# kulgurpowerMCU3-unrouted.net
KiCad netlist of a schematic drawn in EAGLE
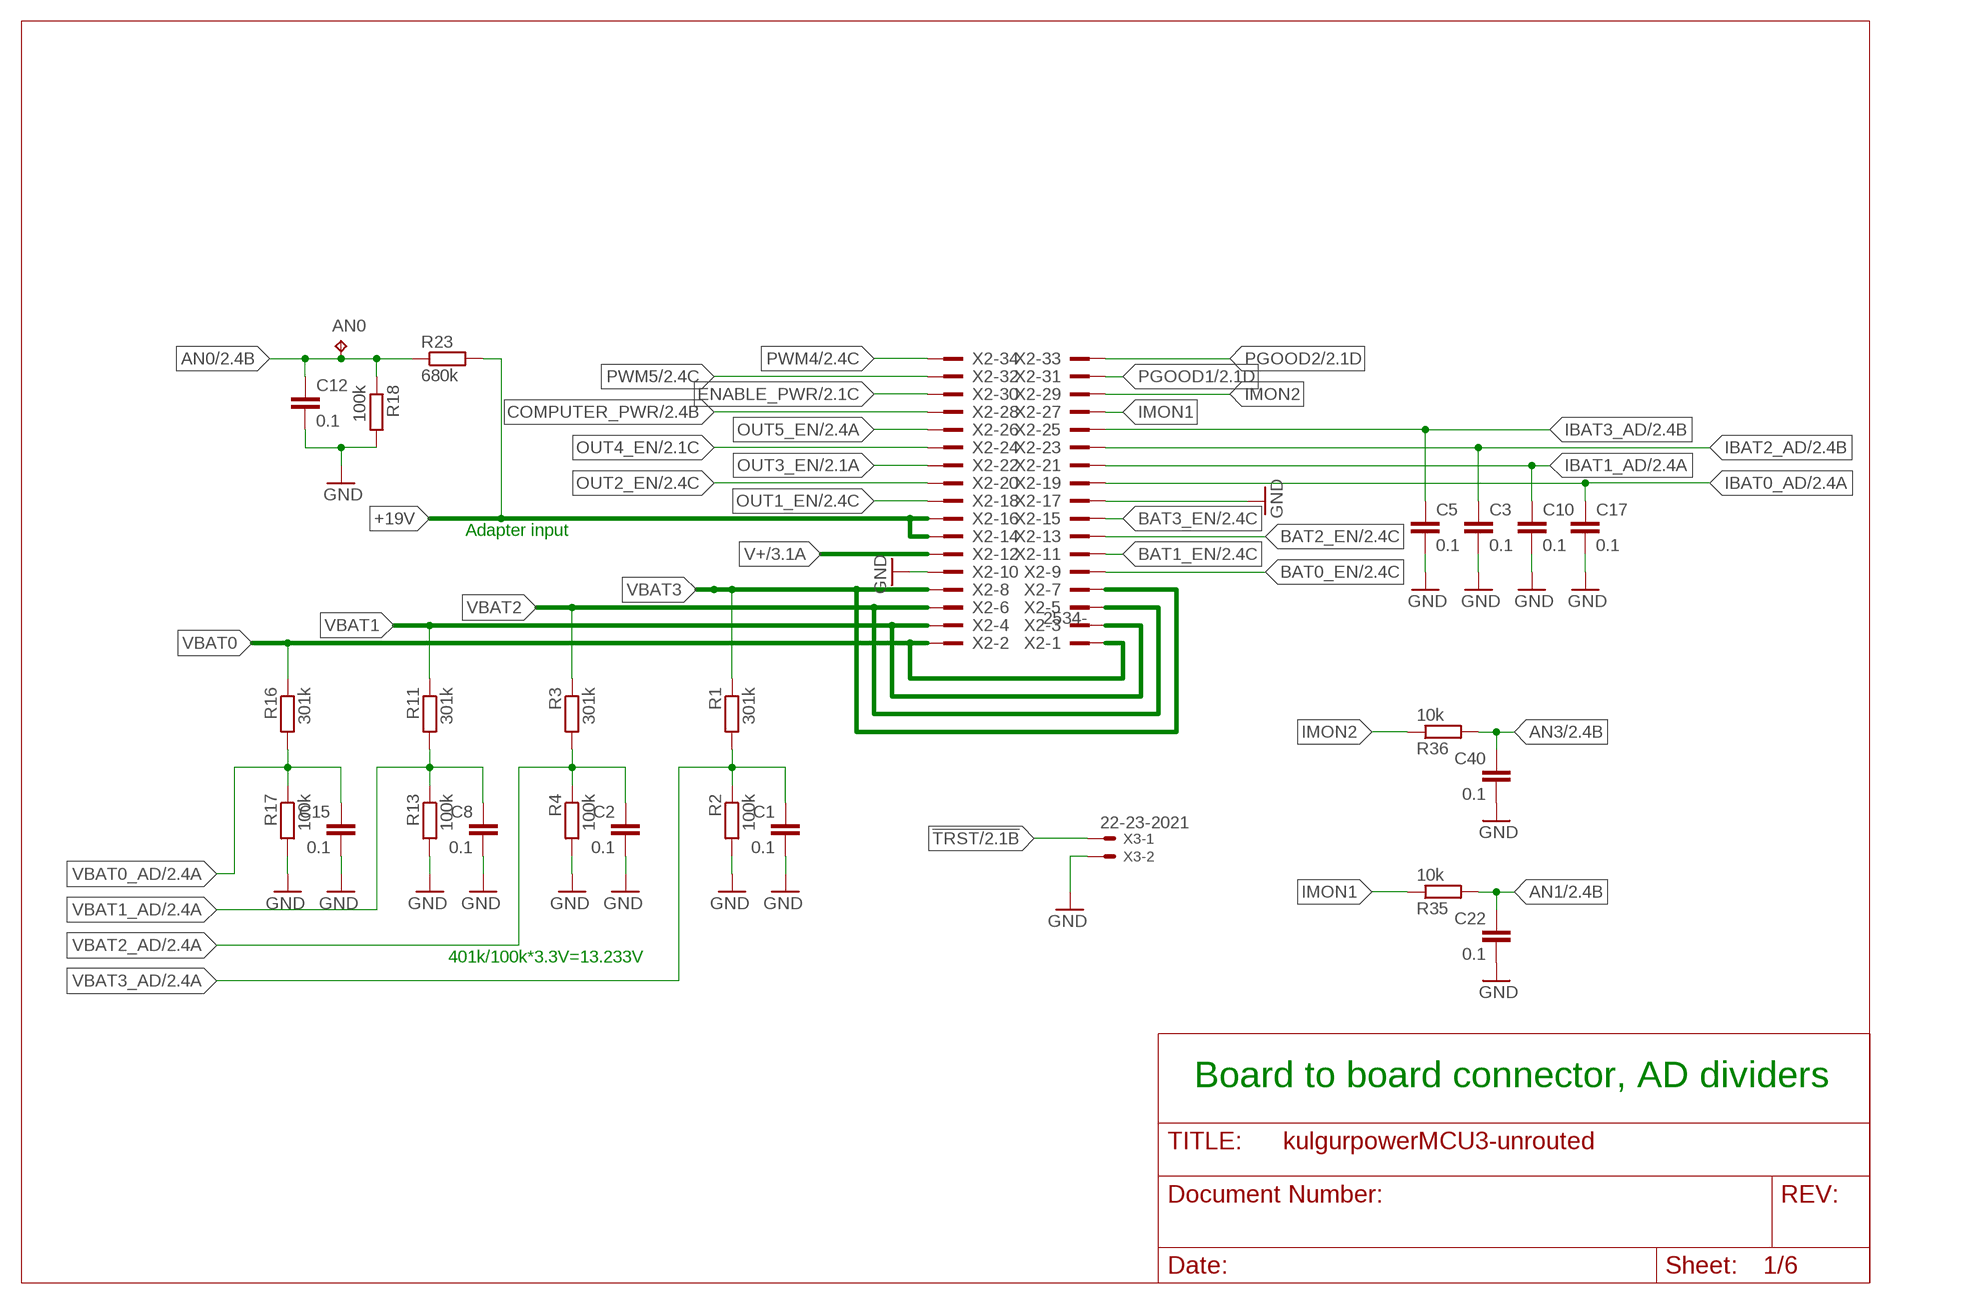
[diagram p0: schematic, sheet 1]
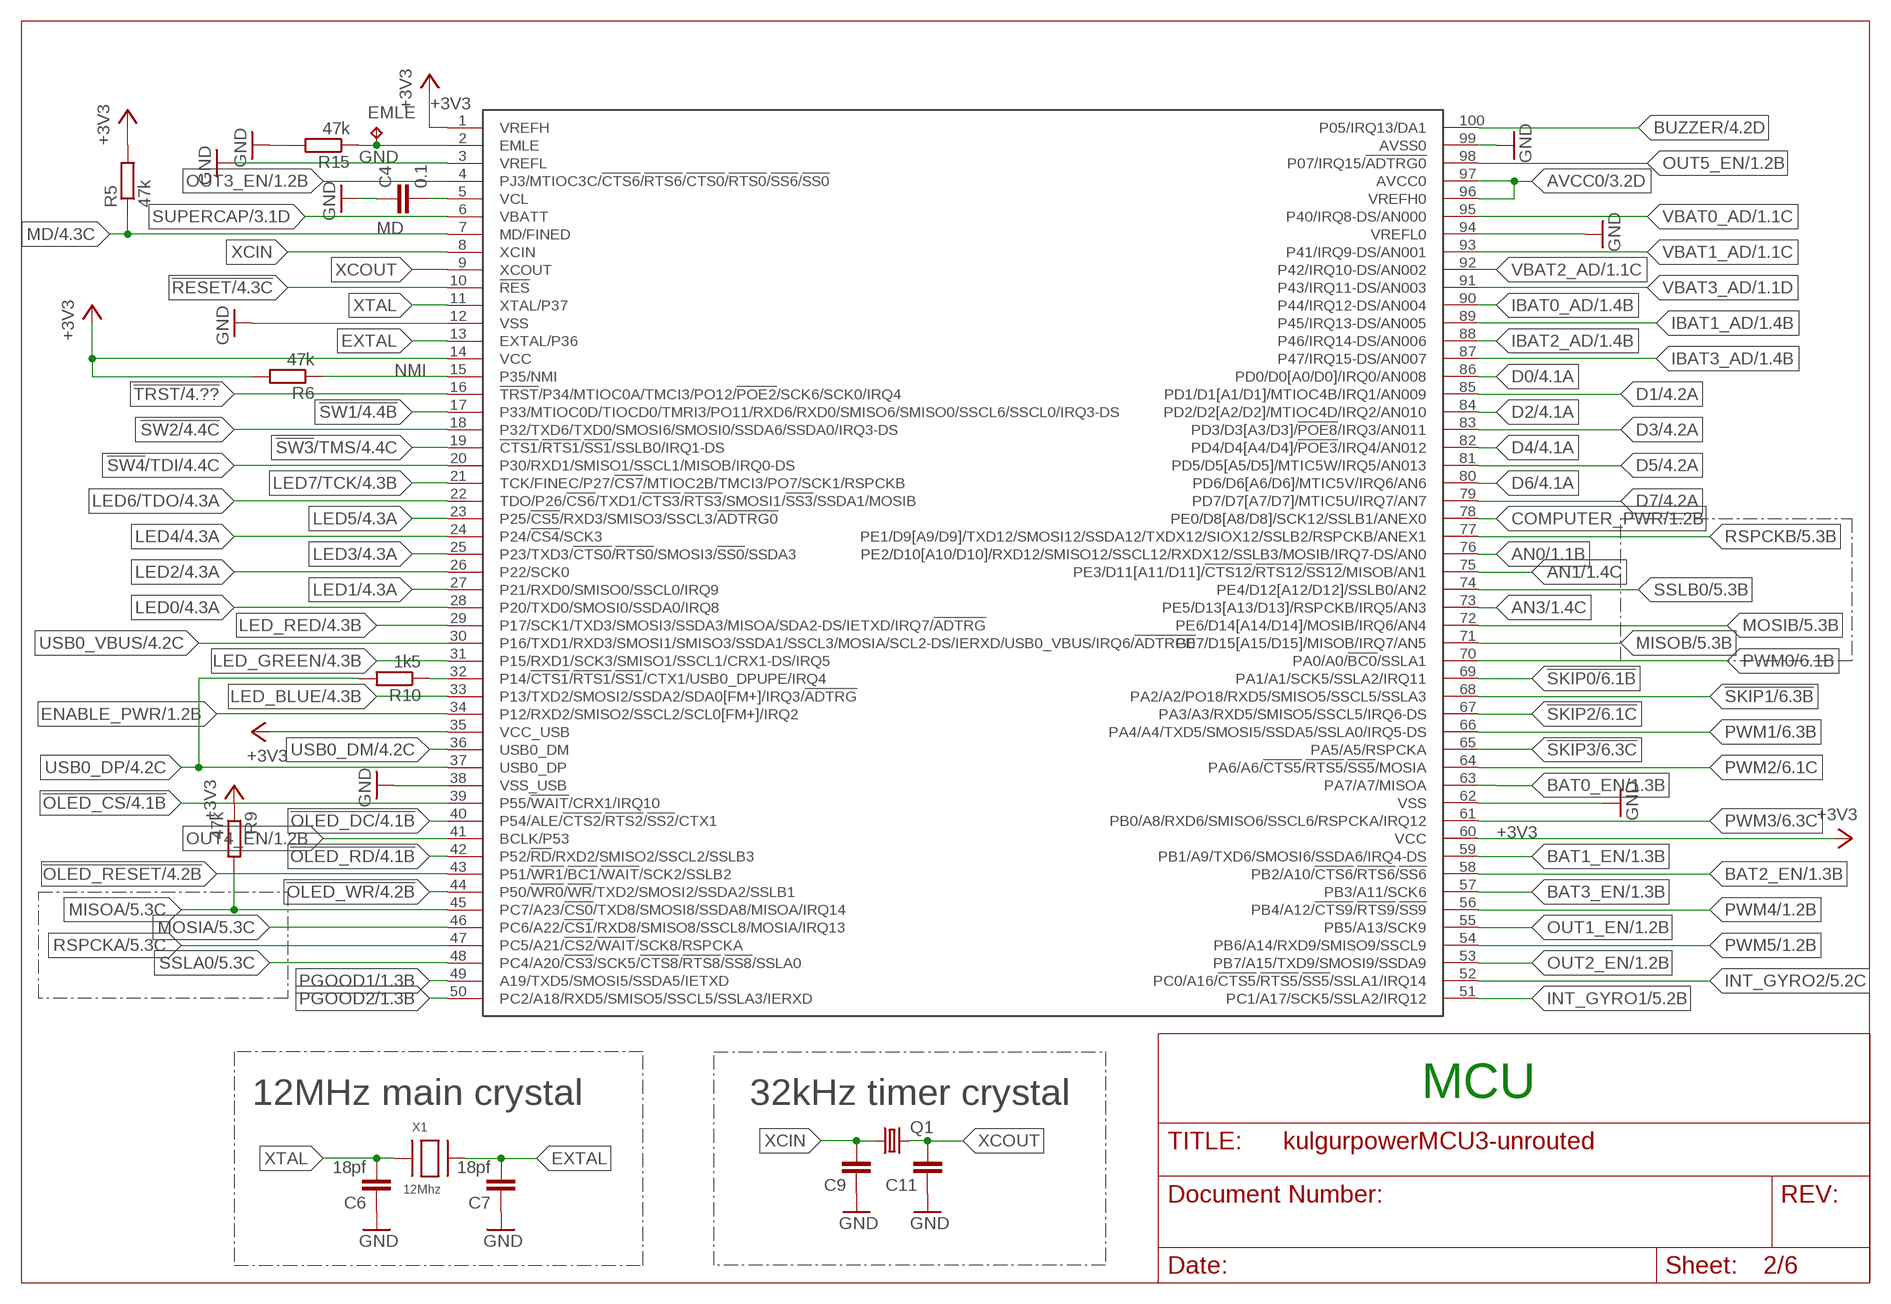
[diagram p1: schematic, sheet 2]
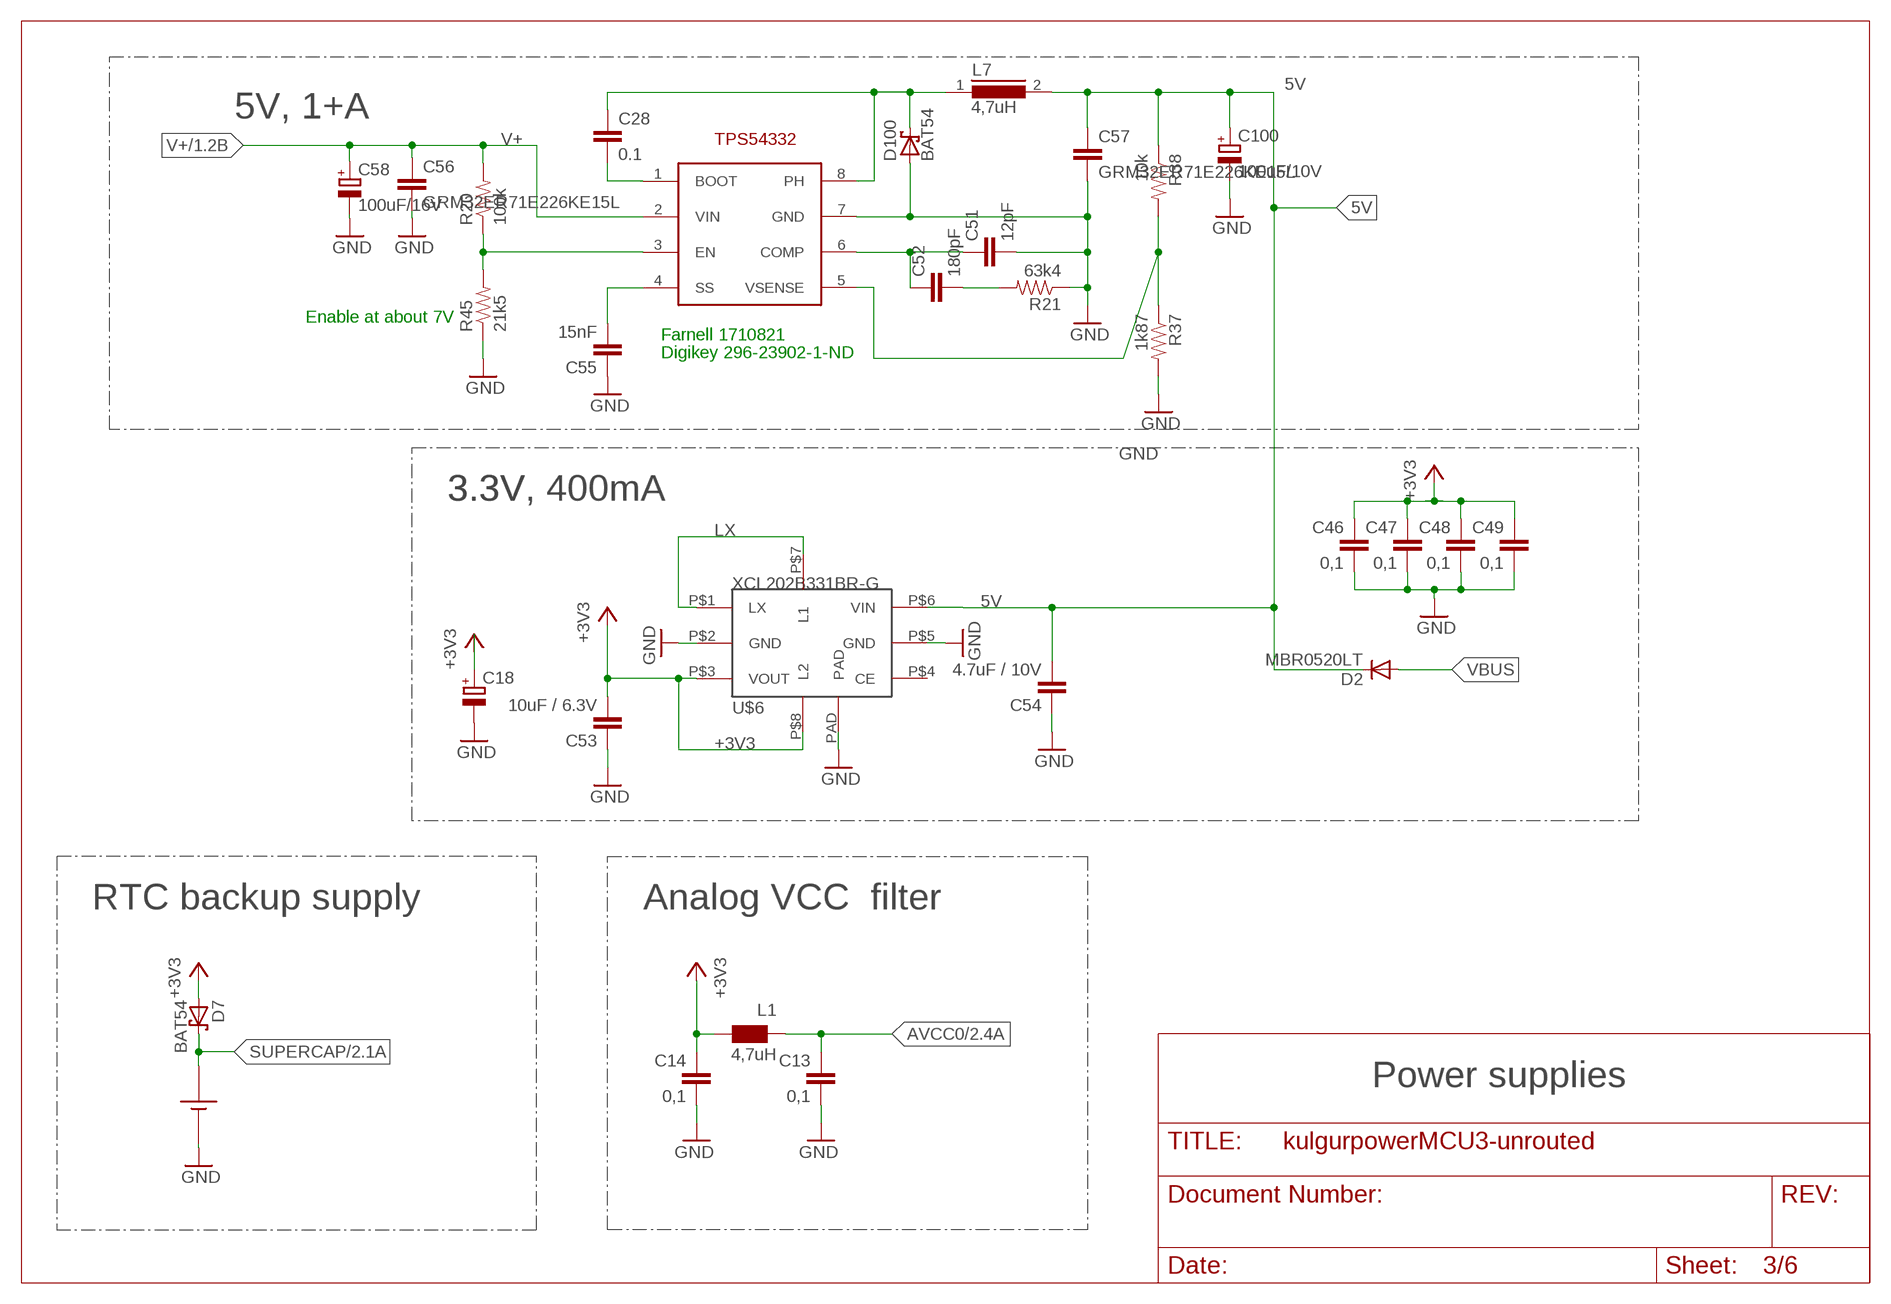
[diagram p2: schematic, sheet 3]
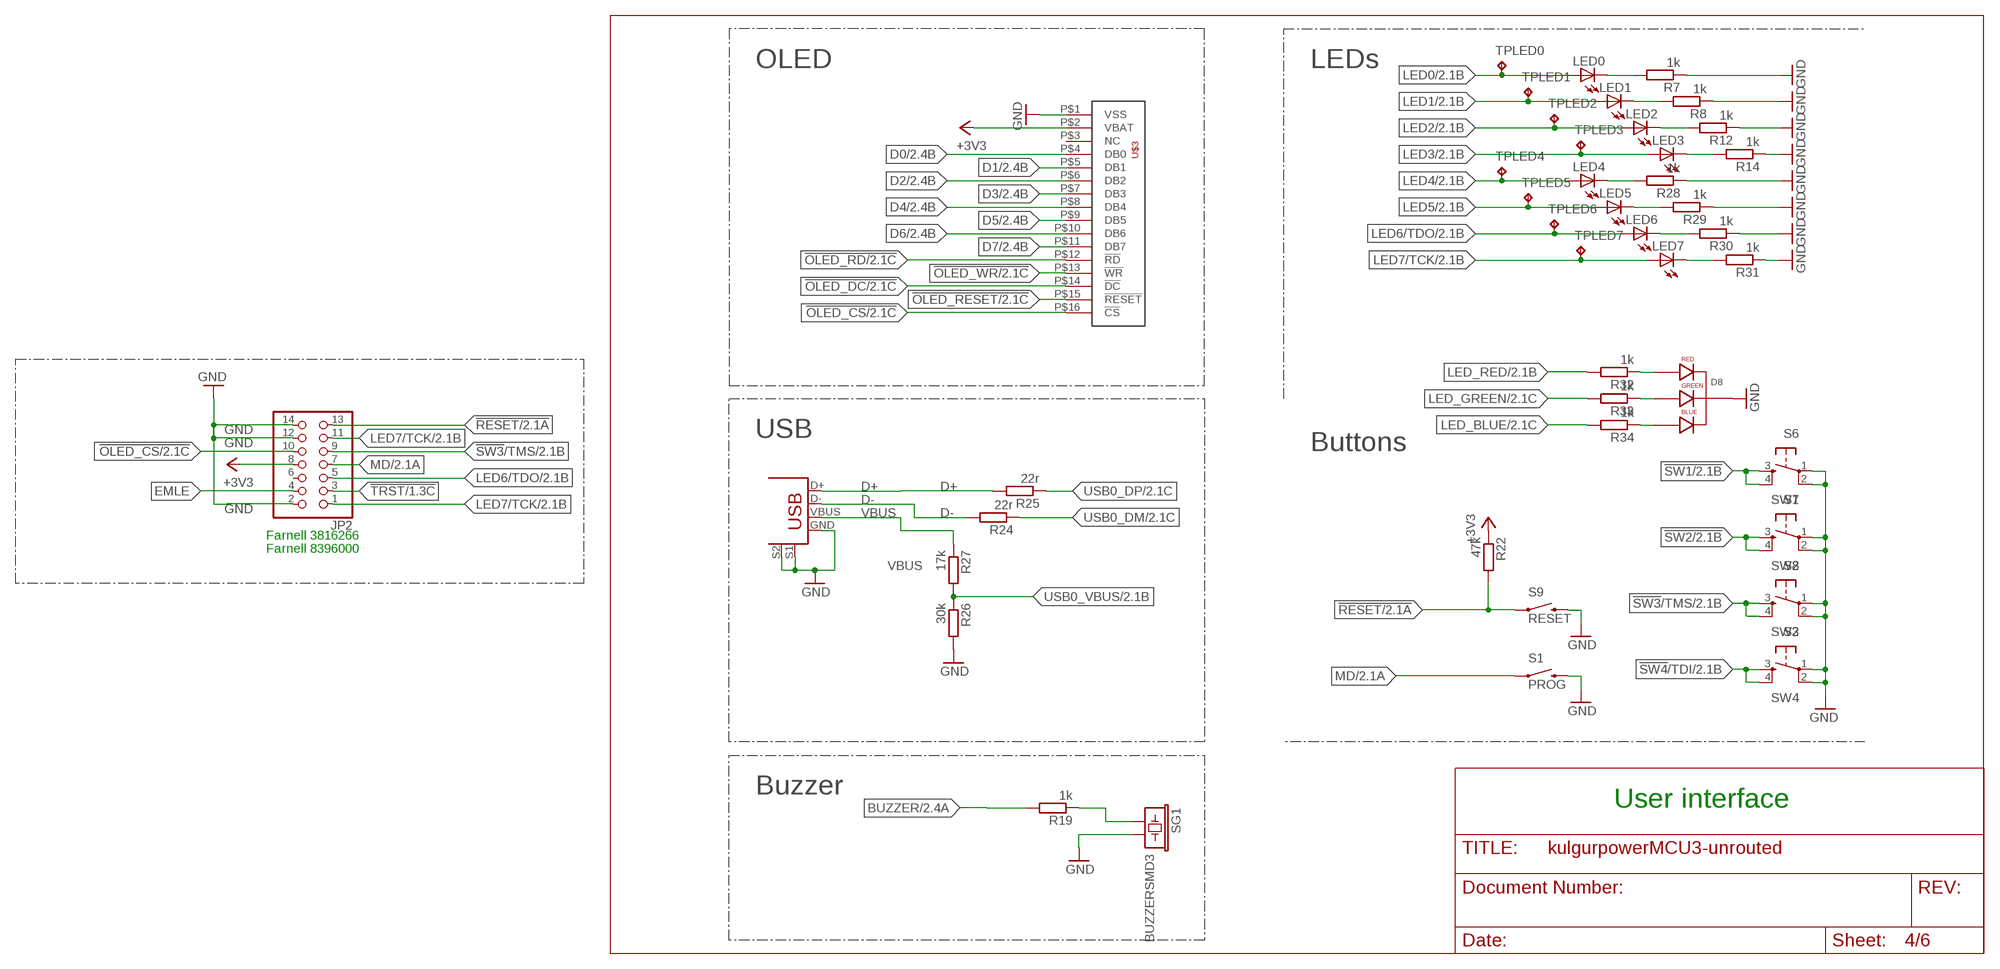
[diagram p3: schematic, sheet 4]
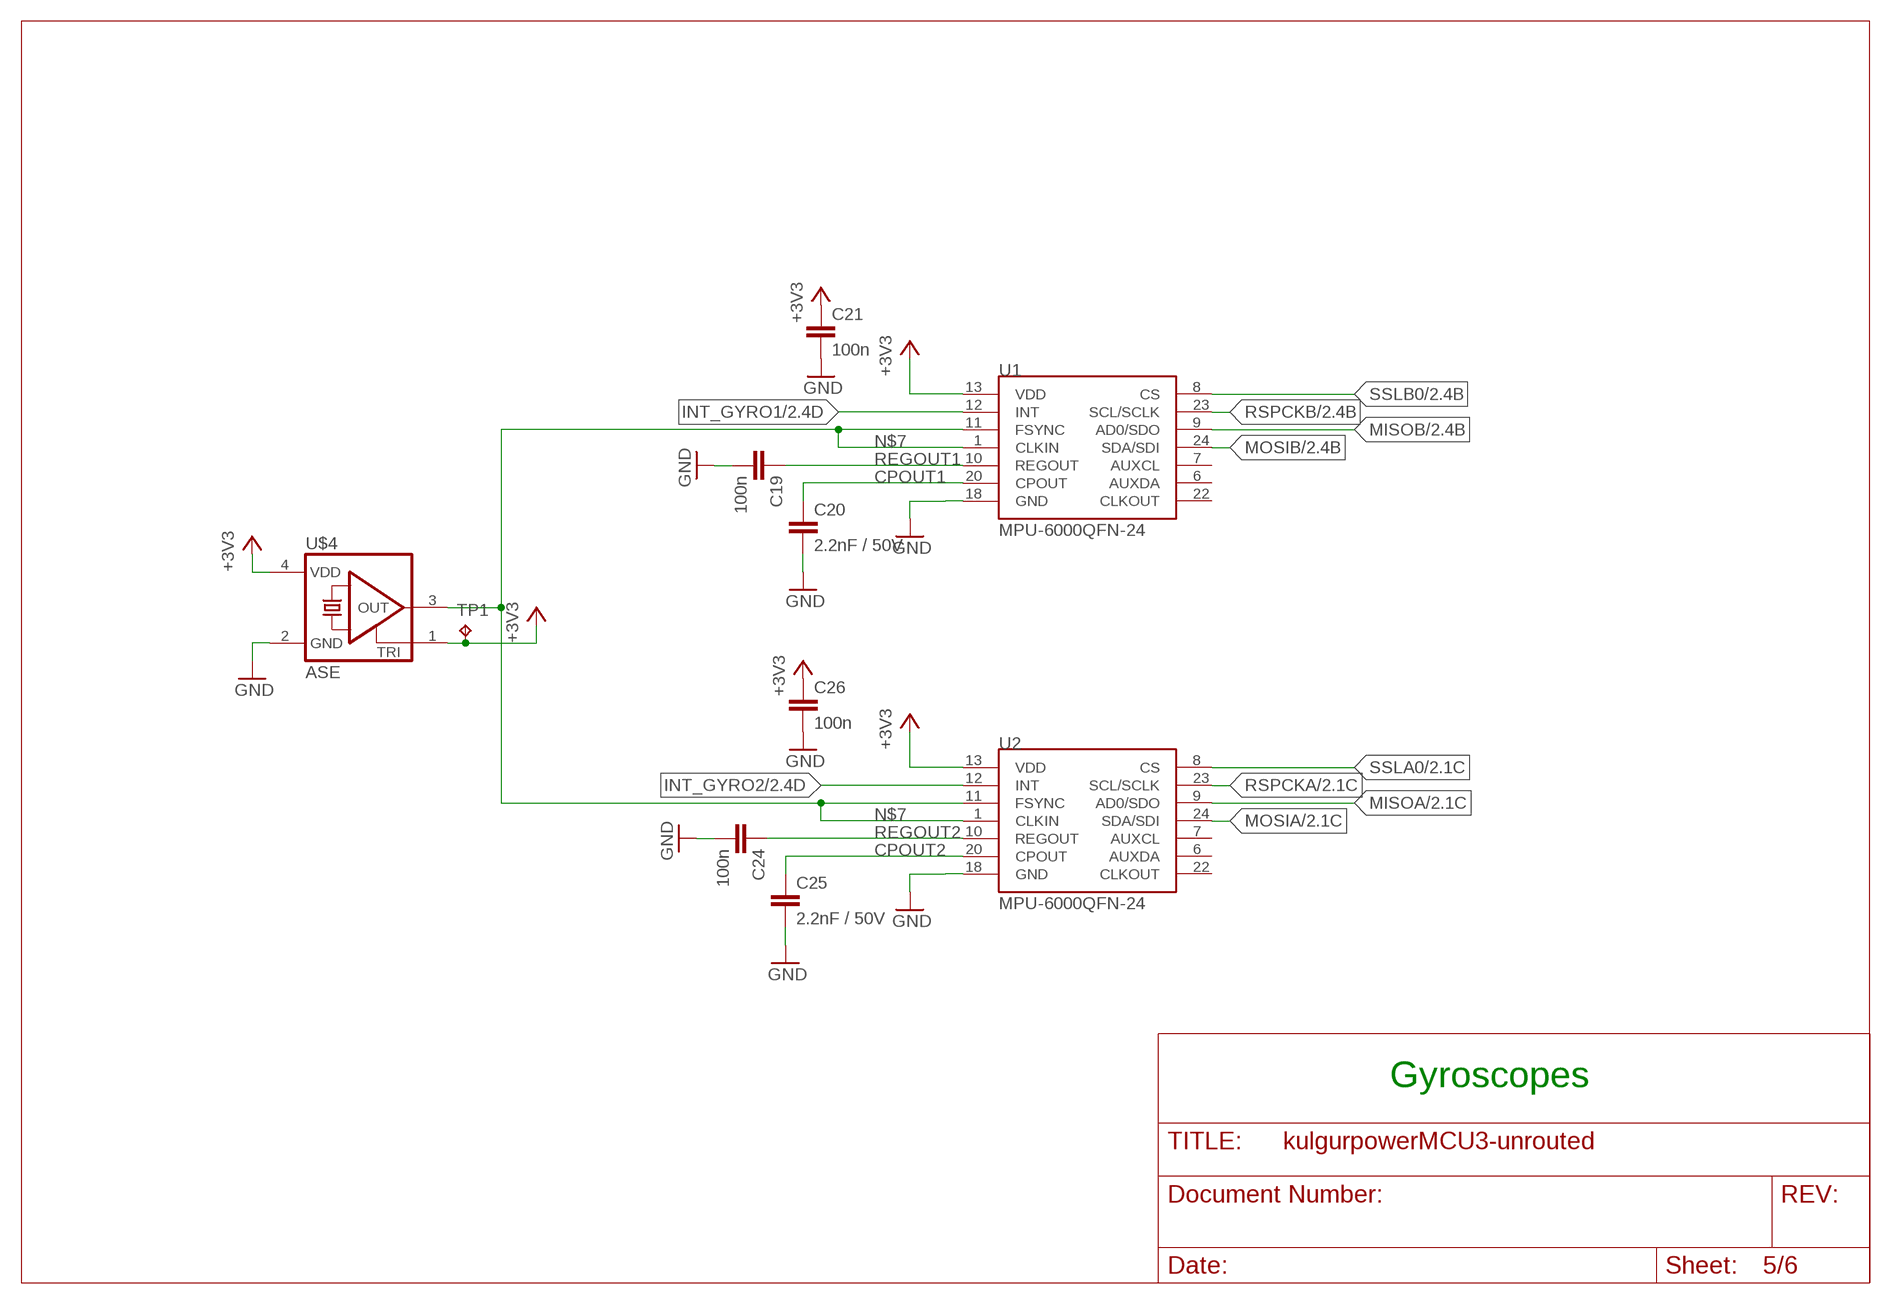
[diagram p4: schematic, sheet 5]
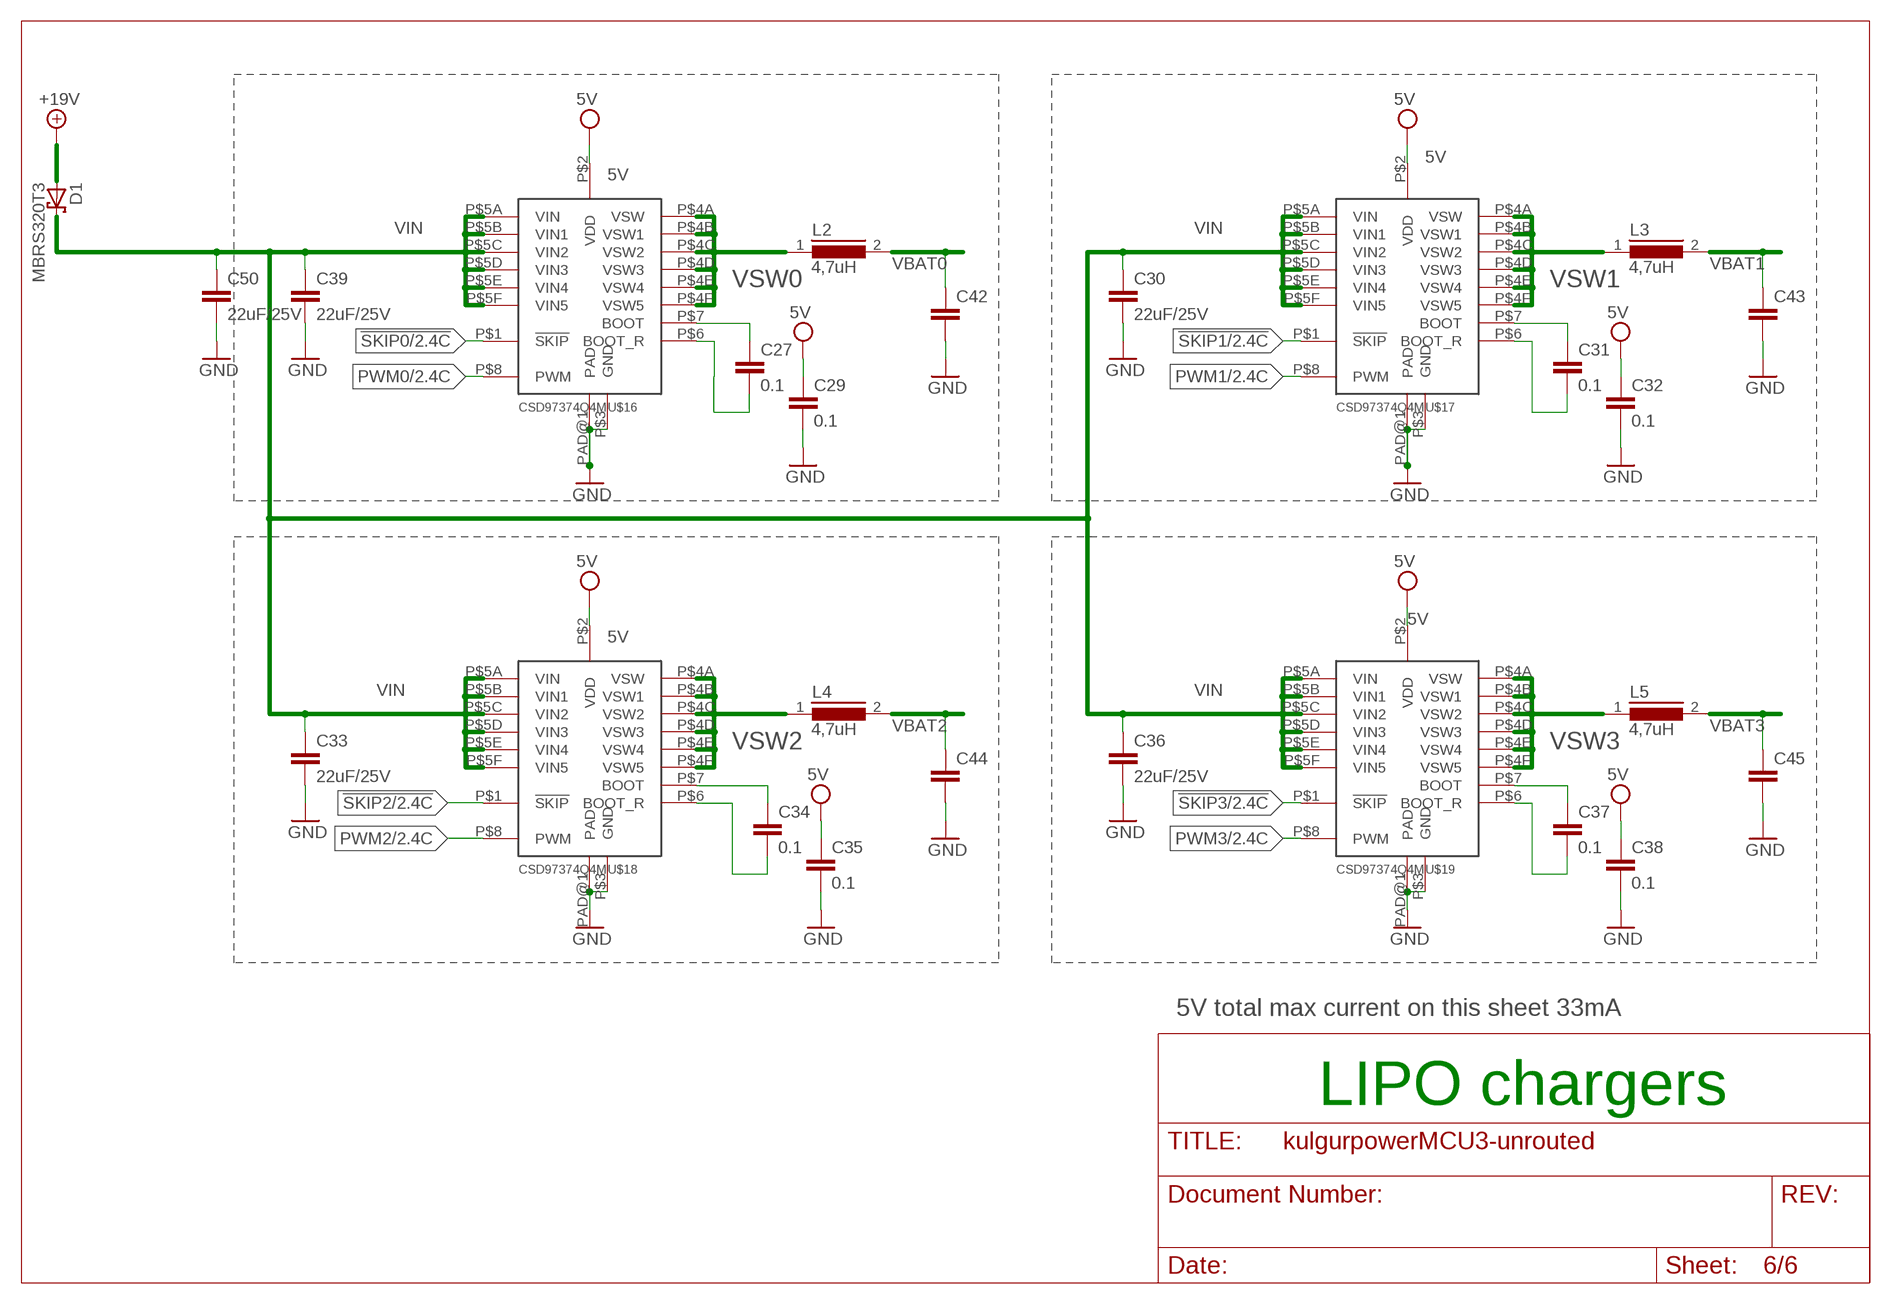
[diagram p5: schematic, sheet 6]

(export (version "E")
  (design (tool "Eeschema 10.0.6"))
  (components
    (comp (ref "AN0")
      (value "TPB1,27")
      (footprint "eagle-import:B1,27")
      (libsource (lib "eagle-import") (part "TPB1,27"))
    )
    (comp (ref "C1")
      (value "0.1")
      (footprint "eagle-import:C0603")
      (libsource (lib "eagle-import") (part "C-EUC0603"))
    )
    (comp (ref "C2")
      (value "0.1")
      (footprint "eagle-import:C0603")
      (libsource (lib "eagle-import") (part "C-EUC0603"))
    )
    (comp (ref "C3")
      (value "0.1")
      (footprint "eagle-import:C0603")
      (libsource (lib "eagle-import") (part "C-EUC0603"))
    )
    (comp (ref "C5")
      (value "0.1")
      (footprint "eagle-import:C0603")
      (libsource (lib "eagle-import") (part "C-EUC0603"))
    )
    (comp (ref "C8")
      (value "0.1")
      (footprint "eagle-import:C0603")
      (libsource (lib "eagle-import") (part "C-EUC0603"))
    )
    (comp (ref "C10")
      (value "0.1")
      (footprint "eagle-import:C0603")
      (libsource (lib "eagle-import") (part "C-EUC0603"))
    )
    (comp (ref "C12")
      (value "0.1")
      (footprint "eagle-import:0603-CAP")
      (libsource (lib "eagle-import") (part "CAP0603-CAP"))
    )
    (comp (ref "C15")
      (value "0.1")
      (footprint "eagle-import:C0603")
      (libsource (lib "eagle-import") (part "C-EUC0603"))
    )
    (comp (ref "C17")
      (value "0.1")
      (footprint "eagle-import:C0603")
      (libsource (lib "eagle-import") (part "C-EUC0603"))
    )
    (comp (ref "C22")
      (value "0.1")
      (footprint "eagle-import:C0603")
      (libsource (lib "eagle-import") (part "C-EUC0603"))
    )
    (comp (ref "C40")
      (value "0.1")
      (footprint "eagle-import:C0603")
      (libsource (lib "eagle-import") (part "C-EUC0603"))
    )
    (comp (ref "R1")
      (value "301k")
      (footprint "eagle-import:R0603")
      (libsource (lib "eagle-import") (part "R-EU_R0603"))
    )
    (comp (ref "R2")
      (value "100k")
      (footprint "eagle-import:R0603")
      (libsource (lib "eagle-import") (part "R-EU_R0603"))
    )
    (comp (ref "R3")
      (value "301k")
      (footprint "eagle-import:R0603")
      (libsource (lib "eagle-import") (part "R-EU_R0603"))
    )
    (comp (ref "R4")
      (value "100k")
      (footprint "eagle-import:R0603")
      (libsource (lib "eagle-import") (part "R-EU_R0603"))
    )
    (comp (ref "R11")
      (value "301k")
      (footprint "eagle-import:R0603")
      (libsource (lib "eagle-import") (part "R-EU_R0603"))
    )
    (comp (ref "R13")
      (value "100k")
      (footprint "eagle-import:R0603")
      (libsource (lib "eagle-import") (part "R-EU_R0603"))
    )
    (comp (ref "R16")
      (value "301k")
      (footprint "eagle-import:R0603")
      (libsource (lib "eagle-import") (part "R-EU_R0603"))
    )
    (comp (ref "R17")
      (value "100k")
      (footprint "eagle-import:R0603")
      (libsource (lib "eagle-import") (part "R-EU_R0603"))
    )
    (comp (ref "R18")
      (value "100k")
      (footprint "eagle-import:R0603")
      (libsource (lib "eagle-import") (part "R-EU_R0603"))
    )
    (comp (ref "R23")
      (value "680k")
      (footprint "eagle-import:R0603")
      (libsource (lib "eagle-import") (part "R-EU_R0603"))
    )
    (comp (ref "R35")
      (value "10k")
      (footprint "eagle-import:R0603")
      (libsource (lib "eagle-import") (part "R-EU_R0603"))
    )
    (comp (ref "R36")
      (value "10k")
      (footprint "eagle-import:R0603")
      (libsource (lib "eagle-import") (part "R-EU_R0603"))
    )
    (comp (ref "X2")
      (value "2534-")
      (footprint "eagle-import:PAK100_2500-34")
      (libsource (lib "eagle-import") (part "2534-"))
    )
    (comp (ref "X3")
      (value "22-23-2021")
      (footprint "eagle-import:22-23-2021")
      (fields (field (name "MF") "MOLEX"))
      (libsource (lib "eagle-import") (part "22-23-2021"))
    )
    (comp (ref "C4")
      (value "0.1")
      (footprint "eagle-import:0603-CAP")
      (libsource (lib "eagle-import") (part "CAP0603-CAP"))
    )
    (comp (ref "C6")
      (value "18pf")
      (footprint "eagle-import:0603-CAP")
      (libsource (lib "eagle-import") (part "CAP0603-CAP"))
    )
    (comp (ref "C7")
      (value "18pf")
      (footprint "eagle-import:0603-CAP")
      (libsource (lib "eagle-import") (part "CAP0603-CAP"))
    )
    (comp (ref "C9")
      (value "CAP0603-CAP")
      (footprint "eagle-import:0603-CAP")
      (libsource (lib "eagle-import") (part "CAP0603-CAP"))
    )
    (comp (ref "C11")
      (value "CAP0603-CAP")
      (footprint "eagle-import:0603-CAP")
      (libsource (lib "eagle-import") (part "CAP0603-CAP"))
    )
    (comp (ref "EMLE")
      (value "TPB1,27")
      (footprint "eagle-import:B1,27")
      (libsource (lib "eagle-import") (part "TPB1,27"))
    )
    (comp (ref "Q1")
      (value "CRYSTALMM20SS")
      (footprint "eagle-import:MM20SS")
      (libsource (lib "eagle-import") (part "CRYSTALMM20SS"))
    )
    (comp (ref "R5")
      (value "47k")
      (footprint "eagle-import:R0603")
      (libsource (lib "eagle-import") (part "R-EU_R0603"))
    )
    (comp (ref "R6")
      (value "47k")
      (footprint "eagle-import:R0603")
      (libsource (lib "eagle-import") (part "R-EU_R0603"))
    )
    (comp (ref "R9")
      (value "47k")
      (footprint "eagle-import:R0603")
      (libsource (lib "eagle-import") (part "R-EU_R0603"))
    )
    (comp (ref "R10")
      (value "1k5")
      (footprint "eagle-import:R0603")
      (libsource (lib "eagle-import") (part "R-EU_R0603"))
    )
    (comp (ref "R15")
      (value "47k")
      (footprint "eagle-import:R0603")
      (libsource (lib "eagle-import") (part "R-EU_R0603"))
    )
    (comp (ref "U$14")
      (value "R5F5630ADDFP")
      (footprint "eagle-import:LTQFP100")
      (libsource (lib "eagle-import") (part "R5F5630ADDFP"))
    )
    (comp (ref "X1")
      (value "12Mhz")
      (footprint "eagle-import:NX5032")
      (libsource (lib "eagle-import") (part "XTALNX5032"))
    )
    (comp (ref "D8")
      (value "WP154A4SUREQBFZGW")
      (footprint "eagle-import:LED-RGB-THRU")
      (fields (field (name "PROD_ID") "DIO-09434"))
      (libsource (lib "eagle-import") (part "LED-RGB-CC-THRUDIFFUSE"))
    )
    (comp (ref "JP2")
      (value "PINHD-2X7")
      (footprint "eagle-import:2X07")
      (libsource (lib "eagle-import") (part "PINHD-2X7"))
    )
    (comp (ref "LED0")
      (value "LED0603")
      (footprint "eagle-import:LED-0603")
      (libsource (lib "eagle-import") (part "LED0603"))
    )
    (comp (ref "LED1")
      (value "LED0603")
      (footprint "eagle-import:LED-0603")
      (libsource (lib "eagle-import") (part "LED0603"))
    )
    (comp (ref "LED2")
      (value "LED0603")
      (footprint "eagle-import:LED-0603")
      (libsource (lib "eagle-import") (part "LED0603"))
    )
    (comp (ref "LED3")
      (value "LED0603")
      (footprint "eagle-import:LED-0603")
      (libsource (lib "eagle-import") (part "LED0603"))
    )
    (comp (ref "LED4")
      (value "LED0603")
      (footprint "eagle-import:LED-0603")
      (libsource (lib "eagle-import") (part "LED0603"))
    )
    (comp (ref "LED5")
      (value "LED0603")
      (footprint "eagle-import:LED-0603")
      (libsource (lib "eagle-import") (part "LED0603"))
    )
    (comp (ref "LED6")
      (value "LED0603")
      (footprint "eagle-import:LED-0603")
      (libsource (lib "eagle-import") (part "LED0603"))
    )
    (comp (ref "LED7")
      (value "LED0603")
      (footprint "eagle-import:LED-0603")
      (libsource (lib "eagle-import") (part "LED0603"))
    )
    (comp (ref "R7")
      (value "1k")
      (footprint "eagle-import:R0603")
      (libsource (lib "eagle-import") (part "R-EU_R0603"))
    )
    (comp (ref "R8")
      (value "1k")
      (footprint "eagle-import:R0603")
      (libsource (lib "eagle-import") (part "R-EU_R0603"))
    )
    (comp (ref "R12")
      (value "1k")
      (footprint "eagle-import:R0603")
      (libsource (lib "eagle-import") (part "R-EU_R0603"))
    )
    (comp (ref "R14")
      (value "1k")
      (footprint "eagle-import:R0603")
      (libsource (lib "eagle-import") (part "R-EU_R0603"))
    )
    (comp (ref "R19")
      (value "1k")
      (footprint "eagle-import:R0603")
      (libsource (lib "eagle-import") (part "R-EU_R0603"))
    )
    (comp (ref "R22")
      (value "47k")
      (footprint "eagle-import:R0603")
      (libsource (lib "eagle-import") (part "R-EU_R0603"))
    )
    (comp (ref "R24")
      (value "22r")
      (footprint "eagle-import:R0603")
      (libsource (lib "eagle-import") (part "R-EU_R0603"))
    )
    (comp (ref "R25")
      (value "22r")
      (footprint "eagle-import:R0603")
      (libsource (lib "eagle-import") (part "R-EU_R0603"))
    )
    (comp (ref "R26")
      (value "30k")
      (footprint "eagle-import:R0603")
      (libsource (lib "eagle-import") (part "R-EU_R0603"))
    )
    (comp (ref "R27")
      (value "17k")
      (footprint "eagle-import:R0603")
      (libsource (lib "eagle-import") (part "R-EU_R0603"))
    )
    (comp (ref "R28")
      (value "1k")
      (footprint "eagle-import:R0603")
      (libsource (lib "eagle-import") (part "R-EU_R0603"))
    )
    (comp (ref "R29")
      (value "1k")
      (footprint "eagle-import:R0603")
      (libsource (lib "eagle-import") (part "R-EU_R0603"))
    )
    (comp (ref "R30")
      (value "1k")
      (footprint "eagle-import:R0603")
      (libsource (lib "eagle-import") (part "R-EU_R0603"))
    )
    (comp (ref "R31")
      (value "1k")
      (footprint "eagle-import:R0603")
      (libsource (lib "eagle-import") (part "R-EU_R0603"))
    )
    (comp (ref "R32")
      (value "1k")
      (footprint "eagle-import:R0603")
      (libsource (lib "eagle-import") (part "R-EU_R0603"))
    )
    (comp (ref "R33")
      (value "1k")
      (footprint "eagle-import:R0603")
      (libsource (lib "eagle-import") (part "R-EU_R0603"))
    )
    (comp (ref "R34")
      (value "1k")
      (footprint "eagle-import:R0603")
      (libsource (lib "eagle-import") (part "R-EU_R0603"))
    )
    (comp (ref "S1")
      (value "PROG")
      (footprint "eagle-import:TACTILE-PTH-SIDEEZ")
      (libsource (lib "eagle-import") (part "SWITCH-MOMENTARY-2SIDE_EZ"))
    )
    (comp (ref "S2")
      (value "SW4")
      (footprint "eagle-import:TACTILE-PTH")
      (libsource (lib "eagle-import") (part "TAC_SWITCHPTH"))
    )
    (comp (ref "S6")
      (value "SW1")
      (footprint "eagle-import:TACTILE-PTH")
      (libsource (lib "eagle-import") (part "TAC_SWITCHPTH"))
    )
    (comp (ref "S7")
      (value "SW2")
      (footprint "eagle-import:TACTILE-PTH")
      (libsource (lib "eagle-import") (part "TAC_SWITCHPTH"))
    )
    (comp (ref "S8")
      (value "SW3")
      (footprint "eagle-import:TACTILE-PTH")
      (libsource (lib "eagle-import") (part "TAC_SWITCHPTH"))
    )
    (comp (ref "S9")
      (value "RESET")
      (footprint "eagle-import:TACTILE-PTH-SIDEEZ")
      (libsource (lib "eagle-import") (part "SWITCH-MOMENTARY-2SIDE_EZ"))
    )
    (comp (ref "SG1")
      (value "BUZZERSMD3")
      (footprint "eagle-import:BUZZER-CMT1102")
      (libsource (lib "eagle-import") (part "BUZZERSMD3"))
    )
    (comp (ref "TPLED0")
      (value "LED0")
      (footprint "eagle-import:B1,27")
      (libsource (lib "eagle-import") (part "TPB1,27"))
    )
    (comp (ref "TPLED1")
      (value "LED0")
      (footprint "eagle-import:B1,27")
      (libsource (lib "eagle-import") (part "TPB1,27"))
    )
    (comp (ref "TPLED2")
      (value "LED0")
      (footprint "eagle-import:B1,27")
      (libsource (lib "eagle-import") (part "TPB1,27"))
    )
    (comp (ref "TPLED3")
      (value "LED0")
      (footprint "eagle-import:B1,27")
      (libsource (lib "eagle-import") (part "TPB1,27"))
    )
    (comp (ref "TPLED4")
      (value "LED0")
      (footprint "eagle-import:B1,27")
      (libsource (lib "eagle-import") (part "TPB1,27"))
    )
    (comp (ref "TPLED5")
      (value "LED0")
      (footprint "eagle-import:B1,27")
      (libsource (lib "eagle-import") (part "TPB1,27"))
    )
    (comp (ref "TPLED6")
      (value "LED0")
      (footprint "eagle-import:B1,27")
      (libsource (lib "eagle-import") (part "TPB1,27"))
    )
    (comp (ref "TPLED7")
      (value "LED0")
      (footprint "eagle-import:B1,27")
      (libsource (lib "eagle-import") (part "TPB1,27"))
    )
    (comp (ref "U$2")
      (value "USB+SHIELD")
      (footprint "eagle-import:USB-B-PTH")
      (libsource (lib "eagle-import") (part "USB+SHIELD"))
    )
    (comp (ref "U$3")
      (value "ER-OLEDM032-1")
      (footprint "eagle-import:ER-OLEDM032-1")
      (libsource (lib "eagle-import") (part "ER-OLEDM032-1"))
    )
    (comp (ref "C27")
      (value "0.1")
      (footprint "eagle-import:C0603")
      (libsource (lib "eagle-import") (part "C-EUC0603"))
    )
    (comp (ref "C29")
      (value "0.1")
      (footprint "eagle-import:C0603")
      (libsource (lib "eagle-import") (part "C-EUC0603"))
    )
    (comp (ref "C30")
      (value "22uF/25V")
      (footprint "eagle-import:C1210")
      (libsource (lib "eagle-import") (part "C-EUC1210"))
    )
    (comp (ref "C31")
      (value "0.1")
      (footprint "eagle-import:C0603")
      (libsource (lib "eagle-import") (part "C-EUC0603"))
    )
    (comp (ref "C32")
      (value "0.1")
      (footprint "eagle-import:C0603")
      (libsource (lib "eagle-import") (part "C-EUC0603"))
    )
    (comp (ref "C33")
      (value "22uF/25V")
      (footprint "eagle-import:C1210")
      (libsource (lib "eagle-import") (part "C-EUC1210"))
    )
    (comp (ref "C34")
      (value "0.1")
      (footprint "eagle-import:C0603")
      (libsource (lib "eagle-import") (part "C-EUC0603"))
    )
    (comp (ref "C35")
      (value "0.1")
      (footprint "eagle-import:C0603")
      (libsource (lib "eagle-import") (part "C-EUC0603"))
    )
    (comp (ref "C36")
      (value "22uF/25V")
      (footprint "eagle-import:C1210")
      (libsource (lib "eagle-import") (part "C-EUC1210"))
    )
    (comp (ref "C37")
      (value "0.1")
      (footprint "eagle-import:C0603")
      (libsource (lib "eagle-import") (part "C-EUC0603"))
    )
    (comp (ref "C38")
      (value "0.1")
      (footprint "eagle-import:C0603")
      (libsource (lib "eagle-import") (part "C-EUC0603"))
    )
    (comp (ref "C39")
      (value "22uF/25V")
      (footprint "eagle-import:C1210")
      (libsource (lib "eagle-import") (part "C-EUC1210"))
    )
    (comp (ref "C42")
      (value "C-EUC1210")
      (footprint "eagle-import:C1210")
      (libsource (lib "eagle-import") (part "C-EUC1210"))
    )
    (comp (ref "C43")
      (value "C-EUC1210")
      (footprint "eagle-import:C1210")
      (libsource (lib "eagle-import") (part "C-EUC1210"))
    )
    (comp (ref "C44")
      (value "C-EUC1210")
      (footprint "eagle-import:C1210")
      (libsource (lib "eagle-import") (part "C-EUC1210"))
    )
    (comp (ref "C45")
      (value "C-EUC1210")
      (footprint "eagle-import:C1210")
      (libsource (lib "eagle-import") (part "C-EUC1210"))
    )
    (comp (ref "C50")
      (value "22uF/25V")
      (footprint "eagle-import:C1210")
      (libsource (lib "eagle-import") (part "C-EUC1210"))
    )
    (comp (ref "D1")
      (value "MBRS320T3")
      (footprint "eagle-import:SMC")
      (libsource (lib "eagle-import") (part "MBRS30T32"))
    )
    (comp (ref "L2")
      (value "4,7uH")
      (footprint "eagle-import:DR73")
      (libsource (lib "eagle-import") (part "DR73"))
    )
    (comp (ref "L3")
      (value "4,7uH")
      (footprint "eagle-import:DR73")
      (libsource (lib "eagle-import") (part "DR73"))
    )
    (comp (ref "L4")
      (value "4,7uH")
      (footprint "eagle-import:DR73")
      (libsource (lib "eagle-import") (part "DR73"))
    )
    (comp (ref "L5")
      (value "4,7uH")
      (footprint "eagle-import:DR73")
      (libsource (lib "eagle-import") (part "DR73"))
    )
    (comp (ref "U$16")
      (value "CSD97374Q4M")
      (footprint "eagle-import:CSD97374Q4M")
      (libsource (lib "eagle-import") (part "CSD97374Q4M"))
    )
    (comp (ref "U$17")
      (value "CSD97374Q4M")
      (footprint "eagle-import:CSD97374Q4M")
      (libsource (lib "eagle-import") (part "CSD97374Q4M"))
    )
    (comp (ref "U$18")
      (value "CSD97374Q4M")
      (footprint "eagle-import:CSD97374Q4M")
      (libsource (lib "eagle-import") (part "CSD97374Q4M"))
    )
    (comp (ref "U$19")
      (value "CSD97374Q4M")
      (footprint "eagle-import:CSD97374Q4M")
      (libsource (lib "eagle-import") (part "CSD97374Q4M"))
    )
    (comp (ref "C13")
      (value "0,1")
      (footprint "eagle-import:0603-CAP")
      (libsource (lib "eagle-import") (part "CAP0603-CAP"))
    )
    (comp (ref "C14")
      (value "0,1")
      (footprint "eagle-import:0603-CAP")
      (libsource (lib "eagle-import") (part "CAP0603-CAP"))
    )
    (comp (ref "C18")
      (value "CPOL-EUC/6032-28R")
      (footprint "eagle-import:C_6032-28R")
      (libsource (lib "eagle-import") (part "CPOL-EUC/6032-28R"))
    )
    (comp (ref "C28")
      (value "0.1")
      (footprint "eagle-import:0603-CAP")
      (libsource (lib "eagle-import") (part "CAP0603-CAP"))
    )
    (comp (ref "C46")
      (value "0,1")
      (footprint "eagle-import:0603-CAP")
      (libsource (lib "eagle-import") (part "CAP0603-CAP"))
    )
    (comp (ref "C47")
      (value "0,1")
      (footprint "eagle-import:0603-CAP")
      (libsource (lib "eagle-import") (part "CAP0603-CAP"))
    )
    (comp (ref "C48")
      (value "0,1")
      (footprint "eagle-import:0603-CAP")
      (libsource (lib "eagle-import") (part "CAP0603-CAP"))
    )
    (comp (ref "C49")
      (value "0,1")
      (footprint "eagle-import:0603-CAP")
      (libsource (lib "eagle-import") (part "CAP0603-CAP"))
    )
    (comp (ref "C51")
      (value "12pF")
      (footprint "eagle-import:0603-CAP")
      (libsource (lib "eagle-import") (part "CAP0603-CAP"))
    )
    (comp (ref "C52")
      (value "180pF")
      (footprint "eagle-import:0603-CAP")
      (libsource (lib "eagle-import") (part "CAP0603-CAP"))
    )
    (comp (ref "C53")
      (value "10uF / 6.3V")
      (footprint "eagle-import:C0603")
      (libsource (lib "eagle-import") (part "C-EUC0603"))
    )
    (comp (ref "C54")
      (value "4.7uF / 10V")
      (footprint "eagle-import:C0603")
      (libsource (lib "eagle-import") (part "C-EUC0603"))
    )
    (comp (ref "C55")
      (value "15nF")
      (footprint "eagle-import:0603-CAP")
      (libsource (lib "eagle-import") (part "CAP0603-CAP"))
    )
    (comp (ref "C56")
      (value "GRM32ER71E226KE15L")
      (footprint "eagle-import:C1210")
      (libsource (lib "eagle-import") (part "C-EUC1210"))
    )
    (comp (ref "C57")
      (value "GRM32ER71E226KE15L")
      (footprint "eagle-import:C1210")
      (libsource (lib "eagle-import") (part "C-EUC1210"))
    )
    (comp (ref "C58")
      (value "100uF/16V")
      (footprint "eagle-import:C_6032-28R")
      (libsource (lib "eagle-import") (part "CPOL-EUC/6032-28R"))
    )
    (comp (ref "C100")
      (value "100uF/10V")
      (footprint "eagle-import:C_6032-28R")
      (libsource (lib "eagle-import") (part "CPOL-EUC/6032-28R"))
    )
    (comp (ref "D2")
      (value "MBR0520LT")
      (footprint "eagle-import:SOD123")
      (libsource (lib "eagle-import") (part "MBR0520LT"))
    )
    (comp (ref "D7")
      (value "BAT54")
      (footprint "eagle-import:SOT23")
      (libsource (lib "eagle-import") (part "BAT54"))
    )
    (comp (ref "D100")
      (value "BAT54")
      (footprint "eagle-import:SOT23")
      (libsource (lib "eagle-import") (part "BAT54"))
    )
    (comp (ref "L1")
      (value "4,7uH")
      (footprint "eagle-import:WE-KI_0805_B")
      (libsource (lib "eagle-import") (part "WE-KIHQ_0805"))
    )
    (comp (ref "L7")
      (value "4,7uH")
      (footprint "eagle-import:DR73")
      (libsource (lib "eagle-import") (part "DR73"))
    )
    (comp (ref "R20")
      (value "100k")
      (footprint "eagle-import:0603-RES")
      (libsource (lib "eagle-import") (part "RESISTOR0603-RES"))
    )
    (comp (ref "R21")
      (value "63k4")
      (footprint "eagle-import:0603-RES")
      (libsource (lib "eagle-import") (part "RESISTOR0603-RES"))
    )
    (comp (ref "R37")
      (value "1k87")
      (footprint "eagle-import:0603-RES")
      (libsource (lib "eagle-import") (part "RESISTOR0603-RES"))
    )
    (comp (ref "R38")
      (value "10k")
      (footprint "eagle-import:0603-RES")
      (libsource (lib "eagle-import") (part "RESISTOR0603-RES"))
    )
    (comp (ref "R45")
      (value "21k5")
      (footprint "eagle-import:0603-RES")
      (libsource (lib "eagle-import") (part "RESISTOR0603-RES"))
    )
    (comp (ref "U$1")
      (value "EDLRD224V3R6C")
      (footprint "eagle-import:EDLRD224V3R6C")
      (libsource (lib "eagle-import") (part "EDLRD224V3R6C"))
    )
    (comp (ref "U$5")
      (value "TPS54332")
      (footprint "eagle-import:SO8")
      (libsource (lib "eagle-import") (part "TPS54332"))
    )
    (comp (ref "U$6")
      (value "XCL202B331BR-G")
      (footprint "eagle-import:CL2025")
      (libsource (lib "eagle-import") (part "XCL202"))
    )
    (comp (ref "C19")
      (value "100n")
      (footprint "eagle-import:C0603")
      (libsource (lib "eagle-import") (part "C-EUC0603"))
    )
    (comp (ref "C20")
      (value "2.2nF / 50V")
      (footprint "eagle-import:C0402")
      (libsource (lib "eagle-import") (part "C0402"))
    )
    (comp (ref "C21")
      (value "100n")
      (footprint "eagle-import:C0603")
      (libsource (lib "eagle-import") (part "C-EUC0603"))
    )
    (comp (ref "C24")
      (value "100n")
      (footprint "eagle-import:C0603")
      (libsource (lib "eagle-import") (part "C-EUC0603"))
    )
    (comp (ref "C25")
      (value "2.2nF / 50V")
      (footprint "eagle-import:C0402")
      (libsource (lib "eagle-import") (part "C0402"))
    )
    (comp (ref "C26")
      (value "100n")
      (footprint "eagle-import:C0603")
      (libsource (lib "eagle-import") (part "C-EUC0603"))
    )
    (comp (ref "TP1")
      (value "TPB1,27")
      (footprint "eagle-import:B1,27")
      (libsource (lib "eagle-import") (part "TPB1,27"))
    )
    (comp (ref "U$4")
      (value "ASE")
      (footprint "eagle-import:ASE")
      (libsource (lib "eagle-import") (part "ASE"))
    )
    (comp (ref "U1")
      (value "MPU-6000QFN-24")
      (footprint "eagle-import:QFN-24-TESTING")
      (libsource (lib "eagle-import") (part "MPU-6000QFN-24"))
    )
    (comp (ref "U2")
      (value "MPU-6000QFN-24")
      (footprint "eagle-import:QFN-24-TESTING")
      (libsource (lib "eagle-import") (part "MPU-6000QFN-24"))
    )
  )
  (nets
    (net (code "1") (name "+3V3") (class "Default")
      (node (ref "C14") (pin "1") (pinfunction "1_1") (pintype "passive"))
      (node (ref "C18") (pin "+") (pinfunction "+_+") (pintype "passive"))
      (node (ref "C21") (pin "1") (pinfunction "1_1") (pintype "passive"))
      (node (ref "C26") (pin "1") (pinfunction "1_1") (pintype "passive"))
      (node (ref "C46") (pin "1") (pinfunction "1_1") (pintype "passive"))
      (node (ref "C47") (pin "1") (pinfunction "1_1") (pintype "passive"))
      (node (ref "C48") (pin "1") (pinfunction "1_1") (pintype "passive"))
      (node (ref "C49") (pin "1") (pinfunction "1_1") (pintype "passive"))
      (node (ref "C53") (pin "2") (pinfunction "2_2") (pintype "passive"))
      (node (ref "D7") (pin "1") (pinfunction "A_1") (pintype "passive"))
      (node (ref "JP2") (pin "8") (pinfunction "8_8") (pintype "passive"))
      (node (ref "L1") (pin "1") (pinfunction "2_1") (pintype "passive"))
      (node (ref "R22") (pin "1") (pinfunction "1_1") (pintype "passive"))
      (node (ref "R5") (pin "2") (pinfunction "2_2") (pintype "passive"))
      (node (ref "R6") (pin "2") (pinfunction "2_2") (pintype "passive"))
      (node (ref "R9") (pin "1") (pinfunction "1_1") (pintype "passive"))
      (node (ref "TP1") (pin "TP") (pinfunction "TP_TP") (pintype "input"))
      (node (ref "U$14") (pin "1") (pinfunction "VREFH_1") (pintype "bidirectional"))
      (node (ref "U$14") (pin "14") (pinfunction "VCC_14") (pintype "bidirectional"))
      (node (ref "U$14") (pin "35") (pinfunction "VCC_USB_35") (pintype "bidirectional"))
      (node (ref "U$14") (pin "60") (pinfunction "VCC_60") (pintype "bidirectional"))
      (node (ref "U$3") (pin "P$2") (pinfunction "VBAT_P$2") (pintype "bidirectional"))
      (node (ref "U$4") (pin "1") (pinfunction "TRI_1") (pintype "input"))
      (node (ref "U$4") (pin "4") (pinfunction "VDD_4") (pintype "power_in"))
      (node (ref "U$6") (pin "P$3") (pinfunction "VOUT_P$3") (pintype "bidirectional"))
      (node (ref "U$6") (pin "P$8") (pinfunction "L2_P$8") (pintype "bidirectional"))
      (node (ref "U1") (pin "13") (pinfunction "VDD_13") (pintype "bidirectional"))
      (node (ref "U2") (pin "13") (pinfunction "VDD_13") (pintype "bidirectional"))
    )
    (net (code "2") (name "+19V") (class "Default")
      (node (ref "D1") (pin "A") (pinfunction "A_A") (pintype "passive"))
      (node (ref "R23") (pin "2") (pinfunction "2_2") (pintype "passive"))
      (node (ref "X2") (pin "14") (pinfunction "KL_14") (pintype "passive"))
      (node (ref "X2") (pin "16") (pinfunction "KL_16") (pintype "passive"))
    )
    (net (code "3") (name "5V") (class "Default")
      (node (ref "C100") (pin "+") (pinfunction "+_+") (pintype "passive"))
      (node (ref "C29") (pin "1") (pinfunction "1_1") (pintype "passive"))
      (node (ref "C32") (pin "1") (pinfunction "1_1") (pintype "passive"))
      (node (ref "C35") (pin "1") (pinfunction "1_1") (pintype "passive"))
      (node (ref "C38") (pin "1") (pinfunction "1_1") (pintype "passive"))
      (node (ref "C54") (pin "2") (pinfunction "2_2") (pintype "passive"))
      (node (ref "C57") (pin "1") (pinfunction "1_1") (pintype "passive"))
      (node (ref "D2") (pin "C") (pinfunction "C_C") (pintype "passive"))
      (node (ref "L7") (pin "2") (pinfunction "2_2") (pintype "passive"))
      (node (ref "R38") (pin "1") (pinfunction "1_1") (pintype "passive"))
      (node (ref "U$16") (pin "P$2") (pinfunction "VDD_P$2") (pintype "bidirectional"))
      (node (ref "U$17") (pin "P$2") (pinfunction "VDD_P$2") (pintype "bidirectional"))
      (node (ref "U$18") (pin "P$2") (pinfunction "VDD_P$2") (pintype "bidirectional"))
      (node (ref "U$19") (pin "P$2") (pinfunction "VDD_P$2") (pintype "bidirectional"))
      (node (ref "U$6") (pin "P$6") (pinfunction "VIN_P$6") (pintype "bidirectional"))
    )
    (net (code "4") (name "AN0") (class "Default")
      (node (ref "AN0") (pin "TP") (pinfunction "TP_TP") (pintype "input"))
      (node (ref "C12") (pin "1") (pinfunction "1_1") (pintype "passive"))
      (node (ref "R18") (pin "1") (pinfunction "1_1") (pintype "passive"))
      (node (ref "R23") (pin "1") (pinfunction "1_1") (pintype "passive"))
      (node (ref "U$14") (pin "76") (pinfunction "PE2/D10[A10/D10]/RXD12/SMISO12/SSCL12/RXDX12/SSLB3/MOSIB/IRQ7-DS/AN0_76") (pintype "bidirectional"))
    )
    (net (code "5") (name "AN1") (class "Default")
      (node (ref "C22") (pin "1") (pinfunction "1_1") (pintype "passive"))
      (node (ref "R35") (pin "2") (pinfunction "2_2") (pintype "passive"))
      (node (ref "U$14") (pin "75") (pinfunction "PE3/D11[A11/D11]/~{CTS12}/~{RTS12}/~{SS12}/MISOB/AN1_75") (pintype "bidirectional"))
    )
    (net (code "6") (name "AN3") (class "Default")
      (node (ref "C40") (pin "1") (pinfunction "1_1") (pintype "passive"))
      (node (ref "R36") (pin "2") (pinfunction "2_2") (pintype "passive"))
      (node (ref "U$14") (pin "73") (pinfunction "PE5/D13[A13/D13]/RSPCKB/IRQ5/AN3_73") (pintype "bidirectional"))
    )
    (net (code "7") (name "AVCC0") (class "Default")
      (node (ref "C13") (pin "1") (pinfunction "1_1") (pintype "passive"))
      (node (ref "L1") (pin "2") (pinfunction "1_2") (pintype "passive"))
      (node (ref "U$14") (pin "96") (pinfunction "VREFH0_96") (pintype "bidirectional"))
      (node (ref "U$14") (pin "97") (pinfunction "AVCC0_97") (pintype "bidirectional"))
    )
    (net (code "8") (name "BAT0_EN") (class "Default")
      (node (ref "U$14") (pin "63") (pinfunction "PA7/A7/MISOA_63") (pintype "bidirectional"))
      (node (ref "X2") (pin "9") (pinfunction "KL_9") (pintype "passive"))
    )
    (net (code "9") (name "BAT1_EN") (class "Default")
      (node (ref "U$14") (pin "59") (pinfunction "PB1/A9/TXD6/SMOSI6/SSDA6/IRQ4-DS_59") (pintype "bidirectional"))
      (node (ref "X2") (pin "11") (pinfunction "KL_11") (pintype "passive"))
    )
    (net (code "10") (name "BAT2_EN") (class "Default")
      (node (ref "U$14") (pin "58") (pinfunction "PB2/A10/~{CTS6}/~{RTS6}/~{SS6}_58") (pintype "bidirectional"))
      (node (ref "X2") (pin "13") (pinfunction "KL_13") (pintype "passive"))
    )
    (net (code "11") (name "BAT3_EN") (class "Default")
      (node (ref "U$14") (pin "57") (pinfunction "PB3/A11/SCK6_57") (pintype "bidirectional"))
      (node (ref "X2") (pin "15") (pinfunction "KL_15") (pintype "passive"))
    )
    (net (code "12") (name "BUZZER") (class "Default")
      (node (ref "R19") (pin "2") (pinfunction "2_2") (pintype "passive"))
      (node (ref "U$14") (pin "100") (pinfunction "P05/IRQ13/DA1_100") (pintype "bidirectional"))
    )
    (net (code "13") (name "COMPUTER_PWR") (class "Default")
      (node (ref "U$14") (pin "78") (pinfunction "PE0/D8[A8/D8]/SCK12/SSLB1/ANEX0_78") (pintype "bidirectional"))
      (node (ref "X2") (pin "28") (pinfunction "KL_28") (pintype "passive"))
    )
    (net (code "14") (name "CPOUT1") (class "Default")
      (node (ref "C20") (pin "1") (pinfunction "1_1") (pintype "passive"))
      (node (ref "U1") (pin "20") (pinfunction "CPOUT_20") (pintype "bidirectional"))
    )
    (net (code "15") (name "CPOUT2") (class "Default")
      (node (ref "C25") (pin "1") (pinfunction "1_1") (pintype "passive"))
      (node (ref "U2") (pin "20") (pinfunction "CPOUT_20") (pintype "bidirectional"))
    )
    (net (code "16") (name "D+") (class "Default")
      (node (ref "R25") (pin "2") (pinfunction "2_2") (pintype "passive"))
      (node (ref "U$2") (pin "D+") (pinfunction "D+_D+") (pintype "bidirectional"))
    )
    (net (code "17") (name "D-") (class "Default")
      (node (ref "R24") (pin "2") (pinfunction "2_2") (pintype "passive"))
      (node (ref "U$2") (pin "D-") (pinfunction "D-_D-") (pintype "bidirectional"))
    )
    (net (code "18") (name "D0") (class "Default")
      (node (ref "U$14") (pin "86") (pinfunction "PD0/D0[A0/D0]/IRQ0/AN008_86") (pintype "bidirectional"))
      (node (ref "U$3") (pin "P$4") (pinfunction "DB0_P$4") (pintype "bidirectional"))
    )
    (net (code "19") (name "D1") (class "Default")
      (node (ref "U$14") (pin "85") (pinfunction "PD1/D1[A1/D1]/MTIOC4B/IRQ1/AN009_85") (pintype "bidirectional"))
      (node (ref "U$3") (pin "P$5") (pinfunction "DB1_P$5") (pintype "bidirectional"))
    )
    (net (code "20") (name "D2") (class "Default")
      (node (ref "U$14") (pin "84") (pinfunction "PD2/D2[A2/D2]/MTIOC4D/IRQ2/AN010_84") (pintype "bidirectional"))
      (node (ref "U$3") (pin "P$6") (pinfunction "DB2_P$6") (pintype "bidirectional"))
    )
    (net (code "21") (name "D3") (class "Default")
      (node (ref "U$14") (pin "83") (pinfunction "PD3/D3[A3/D3]/~{POE8}/IRQ3/AN011_83") (pintype "bidirectional"))
      (node (ref "U$3") (pin "P$7") (pinfunction "DB3_P$7") (pintype "bidirectional"))
    )
    (net (code "22") (name "D4") (class "Default")
      (node (ref "U$14") (pin "82") (pinfunction "PD4/D4[A4/D4]/~{POE3}/IRQ4/AN012_82") (pintype "bidirectional"))
      (node (ref "U$3") (pin "P$8") (pinfunction "DB4_P$8") (pintype "bidirectional"))
    )
    (net (code "23") (name "D5") (class "Default")
      (node (ref "U$14") (pin "81") (pinfunction "PD5/D5[A5/D5]/MTIC5W/IRQ5/AN013_81") (pintype "bidirectional"))
      (node (ref "U$3") (pin "P$9") (pinfunction "DB5_P$9") (pintype "bidirectional"))
    )
    (net (code "24") (name "D6") (class "Default")
      (node (ref "U$14") (pin "80") (pinfunction "PD6/D6[A6/D6]/MTIC5V/IRQ6/AN6_80") (pintype "bidirectional"))
      (node (ref "U$3") (pin "P$10") (pinfunction "DB6_P$10") (pintype "bidirectional"))
    )
    (net (code "25") (name "D7") (class "Default")
      (node (ref "U$14") (pin "79") (pinfunction "PD7/D7[A7/D7]/MTIC5U/IRQ7/AN7_79") (pintype "bidirectional"))
      (node (ref "U$3") (pin "P$11") (pinfunction "DB7_P$11") (pintype "bidirectional"))
    )
    (net (code "26") (name "EMLE") (class "Default")
      (node (ref "EMLE") (pin "TP") (pinfunction "TP_TP") (pintype "input"))
      (node (ref "JP2") (pin "4") (pinfunction "4_4") (pintype "passive"))
      (node (ref "R15") (pin "1") (pinfunction "1_1") (pintype "passive"))
      (node (ref "U$14") (pin "2") (pinfunction "EMLE_2") (pintype "bidirectional"))
    )
    (net (code "27") (name "ENABLE_PWR") (class "Default")
      (node (ref "U$14") (pin "34") (pinfunction "P12/RXD2/SMISO2/SSCL2/SCL0[FM+]/IRQ2_34") (pintype "bidirectional"))
      (node (ref "X2") (pin "30") (pinfunction "KL_30") (pintype "passive"))
    )
    (net (code "28") (name "EXTAL") (class "Default")
      (node (ref "C7") (pin "2") (pinfunction "2_2") (pintype "passive"))
      (node (ref "U$14") (pin "13") (pinfunction "EXTAL/P36_13") (pintype "bidirectional"))
      (node (ref "X1") (pin "P$2") (pinfunction "P$2_P$2") (pintype "bidirectional"))
    )
    (net (code "29") (name "GND") (class "Default")
      (node (ref "C1") (pin "2") (pinfunction "2_2") (pintype "passive"))
      (node (ref "C10") (pin "2") (pinfunction "2_2") (pintype "passive"))
      (node (ref "C100") (pin "-") (pinfunction "-_-") (pintype "passive"))
      (node (ref "C11") (pin "1") (pinfunction "1_1") (pintype "passive"))
      (node (ref "C12") (pin "2") (pinfunction "2_2") (pintype "passive"))
      (node (ref "C13") (pin "2") (pinfunction "2_2") (pintype "passive"))
      (node (ref "C14") (pin "2") (pinfunction "2_2") (pintype "passive"))
      (node (ref "C15") (pin "2") (pinfunction "2_2") (pintype "passive"))
      (node (ref "C17") (pin "2") (pinfunction "2_2") (pintype "passive"))
      (node (ref "C18") (pin "-") (pinfunction "-_-") (pintype "passive"))
      (node (ref "C19") (pin "2") (pinfunction "2_2") (pintype "passive"))
      (node (ref "C2") (pin "2") (pinfunction "2_2") (pintype "passive"))
      (node (ref "C20") (pin "2") (pinfunction "2_2") (pintype "passive"))
      (node (ref "C21") (pin "2") (pinfunction "2_2") (pintype "passive"))
      (node (ref "C22") (pin "2") (pinfunction "2_2") (pintype "passive"))
      (node (ref "C24") (pin "2") (pinfunction "2_2") (pintype "passive"))
      (node (ref "C25") (pin "2") (pinfunction "2_2") (pintype "passive"))
      (node (ref "C26") (pin "2") (pinfunction "2_2") (pintype "passive"))
      (node (ref "C29") (pin "2") (pinfunction "2_2") (pintype "passive"))
      (node (ref "C3") (pin "2") (pinfunction "2_2") (pintype "passive"))
      (node (ref "C30") (pin "2") (pinfunction "2_2") (pintype "passive"))
      (node (ref "C32") (pin "2") (pinfunction "2_2") (pintype "passive"))
      (node (ref "C33") (pin "2") (pinfunction "2_2") (pintype "passive"))
      (node (ref "C35") (pin "2") (pinfunction "2_2") (pintype "passive"))
      (node (ref "C36") (pin "2") (pinfunction "2_2") (pintype "passive"))
      (node (ref "C38") (pin "2") (pinfunction "2_2") (pintype "passive"))
      (node (ref "C39") (pin "2") (pinfunction "2_2") (pintype "passive"))
      (node (ref "C4") (pin "1") (pinfunction "1_1") (pintype "passive"))
      (node (ref "C40") (pin "2") (pinfunction "2_2") (pintype "passive"))
      (node (ref "C42") (pin "2") (pinfunction "2_2") (pintype "passive"))
      (node (ref "C43") (pin "2") (pinfunction "2_2") (pintype "passive"))
      (node (ref "C44") (pin "2") (pinfunction "2_2") (pintype "passive"))
      (node (ref "C45") (pin "2") (pinfunction "2_2") (pintype "passive"))
      (node (ref "C46") (pin "2") (pinfunction "2_2") (pintype "passive"))
      (node (ref "C47") (pin "2") (pinfunction "2_2") (pintype "passive"))
      (node (ref "C48") (pin "2") (pinfunction "2_2") (pintype "passive"))
      (node (ref "C49") (pin "2") (pinfunction "2_2") (pintype "passive"))
      (node (ref "C5") (pin "2") (pinfunction "2_2") (pintype "passive"))
      (node (ref "C50") (pin "2") (pinfunction "2_2") (pintype "passive"))
      (node (ref "C51") (pin "2") (pinfunction "2_2") (pintype "passive"))
      (node (ref "C53") (pin "1") (pinfunction "1_1") (pintype "passive"))
      (node (ref "C54") (pin "1") (pinfunction "1_1") (pintype "passive"))
      (node (ref "C55") (pin "1") (pinfunction "1_1") (pintype "passive"))
      (node (ref "C56") (pin "2") (pinfunction "2_2") (pintype "passive"))
      (node (ref "C57") (pin "2") (pinfunction "2_2") (pintype "passive"))
      (node (ref "C58") (pin "-") (pinfunction "-_-") (pintype "passive"))
      (node (ref "C6") (pin "1") (pinfunction "1_1") (pintype "passive"))
      (node (ref "C7") (pin "1") (pinfunction "1_1") (pintype "passive"))
      (node (ref "C8") (pin "2") (pinfunction "2_2") (pintype "passive"))
      (node (ref "C9") (pin "1") (pinfunction "1_1") (pintype "passive"))
      (node (ref "D100") (pin "1") (pinfunction "A_1") (pintype "passive"))
      (node (ref "D8") (pin "2") (pinfunction "CATHODE_2") (pintype "bidirectional"))
      (node (ref "JP2") (pin "12") (pinfunction "12_12") (pintype "passive"))
      (node (ref "JP2") (pin "14") (pinfunction "14_14") (pintype "passive"))
      (node (ref "JP2") (pin "2") (pinfunction "2_2") (pintype "passive"))
      (node (ref "R12") (pin "1") (pinfunction "1_1") (pintype "passive"))
      (node (ref "R13") (pin "2") (pinfunction "2_2") (pintype "passive"))
      (node (ref "R14") (pin "1") (pinfunction "1_1") (pintype "passive"))
      (node (ref "R15") (pin "2") (pinfunction "2_2") (pintype "passive"))
      (node (ref "R17") (pin "2") (pinfunction "2_2") (pintype "passive"))
      (node (ref "R18") (pin "2") (pinfunction "2_2") (pintype "passive"))
      (node (ref "R2") (pin "2") (pinfunction "2_2") (pintype "passive"))
      (node (ref "R21") (pin "1") (pinfunction "1_1") (pintype "passive"))
      (node (ref "R26") (pin "2") (pinfunction "2_2") (pintype "passive"))
      (node (ref "R28") (pin "1") (pinfunction "1_1") (pintype "passive"))
      (node (ref "R29") (pin "1") (pinfunction "1_1") (pintype "passive"))
      (node (ref "R30") (pin "1") (pinfunction "1_1") (pintype "passive"))
      (node (ref "R31") (pin "1") (pinfunction "1_1") (pintype "passive"))
      (node (ref "R37") (pin "2") (pinfunction "2_2") (pintype "passive"))
      (node (ref "R4") (pin "2") (pinfunction "2_2") (pintype "passive"))
      (node (ref "R45") (pin "1") (pinfunction "1_1") (pintype "passive"))
      (node (ref "R7") (pin "1") (pinfunction "1_1") (pintype "passive"))
      (node (ref "R8") (pin "1") (pinfunction "1_1") (pintype "passive"))
      (node (ref "S1") (pin "2") (pinfunction "2_2") (pintype "passive"))
      (node (ref "S2") (pin "1") (pinfunction "1_1") (pintype "passive"))
      (node (ref "S2") (pin "2") (pinfunction "2_2") (pintype "passive"))
      (node (ref "S6") (pin "1") (pinfunction "1_1") (pintype "passive"))
      (node (ref "S6") (pin "2") (pinfunction "2_2") (pintype "passive"))
      (node (ref "S7") (pin "1") (pinfunction "1_1") (pintype "passive"))
      (node (ref "S7") (pin "2") (pinfunction "2_2") (pintype "passive"))
      (node (ref "S8") (pin "1") (pinfunction "1_1") (pintype "passive"))
      (node (ref "S8") (pin "2") (pinfunction "2_2") (pintype "passive"))
      (node (ref "S9") (pin "2") (pinfunction "2_2") (pintype "passive"))
      (node (ref "SG1") (pin "2") (pinfunction "2_2") (pintype "passive"))
      (node (ref "U$1") (pin "N") (pinfunction "N_N") (pintype "bidirectional"))
      (node (ref "U$14") (pin "12") (pinfunction "VSS_12") (pintype "bidirectional"))
      (node (ref "U$14") (pin "3") (pinfunction "VREFL_3") (pintype "bidirectional"))
      (node (ref "U$14") (pin "38") (pinfunction "VSS_USB_38") (pintype "bidirectional"))
      (node (ref "U$14") (pin "62") (pinfunction "VSS_62") (pintype "bidirectional"))
      (node (ref "U$14") (pin "94") (pinfunction "VREFL0_94") (pintype "bidirectional"))
      (node (ref "U$14") (pin "99") (pinfunction "AVSS0_99") (pintype "bidirectional"))
      (node (ref "U$16") (pin "P$3") (pinfunction "GND_P$3") (pintype "bidirectional"))
      (node (ref "U$16") (pin "PAD@1") (pinfunction "PAD_PAD@1") (pintype "bidirectional"))
      (node (ref "U$17") (pin "P$3") (pinfunction "GND_P$3") (pintype "bidirectional"))
      (node (ref "U$17") (pin "PAD@1") (pinfunction "PAD_PAD@1") (pintype "bidirectional"))
      (node (ref "U$18") (pin "P$3") (pinfunction "GND_P$3") (pintype "bidirectional"))
      (node (ref "U$18") (pin "PAD@1") (pinfunction "PAD_PAD@1") (pintype "bidirectional"))
      (node (ref "U$19") (pin "P$3") (pinfunction "GND_P$3") (pintype "bidirectional"))
      (node (ref "U$19") (pin "PAD@1") (pinfunction "PAD_PAD@1") (pintype "bidirectional"))
      (node (ref "U$2") (pin "GND") (pinfunction "GND_GND") (pintype "bidirectional"))
      (node (ref "U$2") (pin "S1") (pinfunction "P$1_S1") (pintype "bidirectional"))
      (node (ref "U$2") (pin "S2") (pinfunction "P$2_S2") (pintype "bidirectional"))
      (node (ref "U$3") (pin "P$1") (pinfunction "VSS_P$1") (pintype "bidirectional"))
      (node (ref "U$4") (pin "2") (pinfunction "GND_2") (pintype "power_in"))
      (node (ref "U$5") (pin "7") (pinfunction "GND_7") (pintype "bidirectional"))
      (node (ref "U$6") (pin "P$2") (pinfunction "GND_P$2") (pintype "bidirectional"))
      (node (ref "U$6") (pin "P$5") (pinfunction "GND_P$5") (pintype "bidirectional"))
      (node (ref "U$6") (pin "PAD") (pinfunction "PAD_PAD") (pintype "bidirectional"))
      (node (ref "U1") (pin "18") (pinfunction "GND_18") (pintype "bidirectional"))
      (node (ref "U2") (pin "18") (pinfunction "GND_18") (pintype "bidirectional"))
      (node (ref "X2") (pin "10") (pinfunction "KL_10") (pintype "passive"))
      (node (ref "X2") (pin "17") (pinfunction "KL_17") (pintype "passive"))
      (node (ref "X3") (pin "2") (pinfunction "S_2") (pintype "passive"))
    )
    (net (code "30") (name "IBAT0_AD") (class "Default")
      (node (ref "C17") (pin "1") (pinfunction "1_1") (pintype "passive"))
      (node (ref "U$14") (pin "90") (pinfunction "P44/IRQ12-DS/AN004_90") (pintype "bidirectional"))
      (node (ref "X2") (pin "19") (pinfunction "KL_19") (pintype "passive"))
    )
    (net (code "31") (name "IBAT1_AD") (class "Default")
      (node (ref "C10") (pin "1") (pinfunction "1_1") (pintype "passive"))
      (node (ref "U$14") (pin "89") (pinfunction "P45/IRQ13-DS/AN005_89") (pintype "bidirectional"))
      (node (ref "X2") (pin "21") (pinfunction "KL_21") (pintype "passive"))
    )
    (net (code "32") (name "IBAT2_AD") (class "Default")
      (node (ref "C3") (pin "1") (pinfunction "1_1") (pintype "passive"))
      (node (ref "U$14") (pin "88") (pinfunction "P46/IRQ14-DS/AN006_88") (pintype "bidirectional"))
      (node (ref "X2") (pin "23") (pinfunction "KL_23") (pintype "passive"))
    )
    (net (code "33") (name "IBAT3_AD") (class "Default")
      (node (ref "C5") (pin "1") (pinfunction "1_1") (pintype "passive"))
      (node (ref "U$14") (pin "87") (pinfunction "P47/IRQ15-DS/AN007_87") (pintype "bidirectional"))
      (node (ref "X2") (pin "25") (pinfunction "KL_25") (pintype "passive"))
    )
    (net (code "34") (name "IMON1") (class "Default")
      (node (ref "R35") (pin "1") (pinfunction "1_1") (pintype "passive"))
      (node (ref "X2") (pin "27") (pinfunction "KL_27") (pintype "passive"))
    )
    (net (code "35") (name "IMON2") (class "Default")
      (node (ref "R36") (pin "1") (pinfunction "1_1") (pintype "passive"))
      (node (ref "X2") (pin "29") (pinfunction "KL_29") (pintype "passive"))
    )
    (net (code "36") (name "INT_GYRO1") (class "Default")
      (node (ref "U$14") (pin "51") (pinfunction "PC1/A17/SCK5/SSLA2/IRQ12_51") (pintype "bidirectional"))
      (node (ref "U1") (pin "12") (pinfunction "INT_12") (pintype "bidirectional"))
    )
    (net (code "37") (name "INT_GYRO2") (class "Default")
      (node (ref "U$14") (pin "52") (pinfunction "PC0/A16/~{CTS5}/~{RTS5}/~{SS5}/SSLA1/IRQ14_52") (pintype "bidirectional"))
      (node (ref "U2") (pin "12") (pinfunction "INT_12") (pintype "bidirectional"))
    )
    (net (code "38") (name "LED0") (class "Default")
      (node (ref "LED0") (pin "A") (pinfunction "A_A") (pintype "passive"))
      (node (ref "TPLED0") (pin "TP") (pinfunction "TP_TP") (pintype "input"))
      (node (ref "U$14") (pin "28") (pinfunction "P20/TXD0/SMOSI0/SSDA0/IRQ8_28") (pintype "bidirectional"))
    )
    (net (code "39") (name "LED1") (class "Default")
      (node (ref "LED1") (pin "A") (pinfunction "A_A") (pintype "passive"))
      (node (ref "TPLED1") (pin "TP") (pinfunction "TP_TP") (pintype "input"))
      (node (ref "U$14") (pin "27") (pinfunction "P21/RXD0/SMISO0/SSCL0/IRQ9_27") (pintype "bidirectional"))
    )
    (net (code "40") (name "LED2") (class "Default")
      (node (ref "LED2") (pin "A") (pinfunction "A_A") (pintype "passive"))
      (node (ref "TPLED2") (pin "TP") (pinfunction "TP_TP") (pintype "input"))
      (node (ref "U$14") (pin "26") (pinfunction "P22/SCK0_26") (pintype "bidirectional"))
    )
    (net (code "41") (name "LED3") (class "Default")
      (node (ref "LED3") (pin "A") (pinfunction "A_A") (pintype "passive"))
      (node (ref "TPLED3") (pin "TP") (pinfunction "TP_TP") (pintype "input"))
      (node (ref "U$14") (pin "25") (pinfunction "P23/TXD3/~{CTS0}/~{RTS0}/SMOSI3/~{SS0}/SSDA3_25") (pintype "bidirectional"))
    )
    (net (code "42") (name "LED4") (class "Default")
      (node (ref "LED4") (pin "A") (pinfunction "A_A") (pintype "passive"))
      (node (ref "TPLED4") (pin "TP") (pinfunction "TP_TP") (pintype "input"))
      (node (ref "U$14") (pin "24") (pinfunction "P24/~{CS4}/SCK3_24") (pintype "bidirectional"))
    )
    (net (code "43") (name "LED5") (class "Default")
      (node (ref "LED5") (pin "A") (pinfunction "A_A") (pintype "passive"))
      (node (ref "TPLED5") (pin "TP") (pinfunction "TP_TP") (pintype "input"))
      (node (ref "U$14") (pin "23") (pinfunction "P25/~{CS5}/RXD3/SMISO3/SSCL3/~{ADTRG0}_23") (pintype "bidirectional"))
    )
    (net (code "44") (name "LED6{slash}TDO") (class "Default")
      (node (ref "JP2") (pin "5") (pinfunction "5_5") (pintype "passive"))
      (node (ref "LED6") (pin "A") (pinfunction "A_A") (pintype "passive"))
      (node (ref "TPLED6") (pin "TP") (pinfunction "TP_TP") (pintype "input"))
      (node (ref "U$14") (pin "22") (pinfunction "TDO/P26/~{CS6}/TXD1/~{CTS3}/~{RTS3}/SMOSI1/~{SS3}/SSDA1/MOSIB_22") (pintype "bidirectional"))
    )
    (net (code "45") (name "LED7{slash}TCK") (class "Default")
      (node (ref "JP2") (pin "1") (pinfunction "1_1") (pintype "passive"))
      (node (ref "JP2") (pin "11") (pinfunction "11_11") (pintype "passive"))
      (node (ref "LED7") (pin "A") (pinfunction "A_A") (pintype "passive"))
      (node (ref "TPLED7") (pin "TP") (pinfunction "TP_TP") (pintype "input"))
      (node (ref "U$14") (pin "21") (pinfunction "TCK/FINEC/P27/~{CS7}/MTIOC2B/TMCI3/PO7/SCK1/RSPCKB_21") (pintype "bidirectional"))
    )
    (net (code "46") (name "LED_BLUE") (class "Default")
      (node (ref "R34") (pin "2") (pinfunction "2_2") (pintype "passive"))
      (node (ref "U$14") (pin "33") (pinfunction "P13/TXD2/SMOSI2/SSDA2/SDA0[FM+]/IRQ3/~{ADTRG}_33") (pintype "bidirectional"))
    )
    (net (code "47") (name "LED_GREEN") (class "Default")
      (node (ref "R33") (pin "2") (pinfunction "2_2") (pintype "passive"))
      (node (ref "U$14") (pin "31") (pinfunction "P15/RXD1/SCK3/SMISO1/SSCL1/CRX1-DS/IRQ5_31") (pintype "bidirectional"))
    )
    (net (code "48") (name "LED_RED") (class "Default")
      (node (ref "R32") (pin "2") (pinfunction "2_2") (pintype "passive"))
      (node (ref "U$14") (pin "29") (pinfunction "P17/SCK1/TXD3/SMOSI3/SSDA3/MISOA/SDA2-DS/IETXD/IRQ7/~{ADTRG}_29") (pintype "bidirectional"))
    )
    (net (code "49") (name "LX") (class "Default")
      (node (ref "U$6") (pin "P$1") (pinfunction "LX_P$1") (pintype "bidirectional"))
      (node (ref "U$6") (pin "P$7") (pinfunction "L1_P$7") (pintype "bidirectional"))
    )
    (net (code "50") (name "MD") (class "Default")
      (node (ref "JP2") (pin "7") (pinfunction "7_7") (pintype "passive"))
      (node (ref "R5") (pin "1") (pinfunction "1_1") (pintype "passive"))
      (node (ref "S1") (pin "1") (pinfunction "1_1") (pintype "passive"))
      (node (ref "U$14") (pin "7") (pinfunction "MD/FINED_7") (pintype "bidirectional"))
    )
    (net (code "51") (name "MISOA") (class "Default")
      (node (ref "R9") (pin "2") (pinfunction "2_2") (pintype "passive"))
      (node (ref "U$14") (pin "45") (pinfunction "PC7/A23/~{CS0}/TXD8/SMOSI8/SSDA8/MISOA/IRQ14_45") (pintype "bidirectional"))
      (node (ref "U2") (pin "9") (pinfunction "AD0/SDO_9") (pintype "bidirectional"))
    )
    (net (code "52") (name "MISOB") (class "Default")
      (node (ref "U$14") (pin "71") (pinfunction "PE7/D15[A15/D15]/MISOB/IRQ7/AN5_71") (pintype "bidirectional"))
      (node (ref "U1") (pin "9") (pinfunction "AD0/SDO_9") (pintype "bidirectional"))
    )
    (net (code "53") (name "MOSIA") (class "Default")
      (node (ref "U$14") (pin "46") (pinfunction "PC6/A22/~{CS1}/RXD8/SMISO8/SSCL8/MOSIA/IRQ13_46") (pintype "bidirectional"))
      (node (ref "U2") (pin "24") (pinfunction "SDA/SDI_24") (pintype "bidirectional"))
    )
    (net (code "54") (name "MOSIB") (class "Default")
      (node (ref "U$14") (pin "72") (pinfunction "PE6/D14[A14/D14]/MOSIB/IRQ6/AN4_72") (pintype "bidirectional"))
      (node (ref "U1") (pin "24") (pinfunction "SDA/SDI_24") (pintype "bidirectional"))
    )
    (net (code "55") (name "N$7") (class "Default")
      (node (ref "U$4") (pin "3") (pinfunction "OUT_3") (pintype "output"))
      (node (ref "U1") (pin "1") (pinfunction "CLKIN_1") (pintype "bidirectional"))
      (node (ref "U1") (pin "11") (pinfunction "FSYNC_11") (pintype "bidirectional"))
      (node (ref "U2") (pin "1") (pinfunction "CLKIN_1") (pintype "bidirectional"))
      (node (ref "U2") (pin "11") (pinfunction "FSYNC_11") (pintype "bidirectional"))
    )
    (net (code "56") (name "NMI") (class "Default")
      (node (ref "R6") (pin "1") (pinfunction "1_1") (pintype "passive"))
      (node (ref "U$14") (pin "15") (pinfunction "P35/NMI_15") (pintype "bidirectional"))
    )
    (net (code "57") (name "Net-(C52-Pad2)") (class "Default")
      (node (ref "C52") (pin "2") (pinfunction "2_2") (pintype "passive"))
      (node (ref "R21") (pin "2") (pinfunction "2_2") (pintype "passive"))
    )
    (net (code "58") (name "Net-(D8-BLUE_CATHODE)") (class "Default")
      (node (ref "D8") (pin "4") (pinfunction "BLUE_CATHODE_4") (pintype "bidirectional"))
      (node (ref "R34") (pin "1") (pinfunction "1_1") (pintype "passive"))
    )
    (net (code "59") (name "Net-(D8-GREEN_CATHODE)") (class "Default")
      (node (ref "D8") (pin "3") (pinfunction "GREEN_CATHODE_3") (pintype "bidirectional"))
      (node (ref "R33") (pin "1") (pinfunction "1_1") (pintype "passive"))
    )
    (net (code "60") (name "Net-(D8-RED_CATHODE)") (class "Default")
      (node (ref "D8") (pin "1") (pinfunction "RED_CATHODE_1") (pintype "bidirectional"))
      (node (ref "R32") (pin "1") (pinfunction "1_1") (pintype "passive"))
    )
    (net (code "61") (name "Net-(D100-C)") (class "Default")
      (node (ref "C28") (pin "1") (pinfunction "1_1") (pintype "passive"))
      (node (ref "D100") (pin "3") (pinfunction "C_3") (pintype "passive"))
      (node (ref "L7") (pin "1") (pinfunction "1_1") (pintype "passive"))
      (node (ref "U$5") (pin "8") (pinfunction "PH_8") (pintype "bidirectional"))
    )
    (net (code "62") (name "Net-(LED0-PadC)") (class "Default")
      (node (ref "LED0") (pin "C") (pinfunction "C_C") (pintype "passive"))
      (node (ref "R7") (pin "2") (pinfunction "2_2") (pintype "passive"))
    )
    (net (code "63") (name "Net-(LED1-PadC)") (class "Default")
      (node (ref "LED1") (pin "C") (pinfunction "C_C") (pintype "passive"))
      (node (ref "R8") (pin "2") (pinfunction "2_2") (pintype "passive"))
    )
    (net (code "64") (name "Net-(LED2-PadC)") (class "Default")
      (node (ref "LED2") (pin "C") (pinfunction "C_C") (pintype "passive"))
      (node (ref "R12") (pin "2") (pinfunction "2_2") (pintype "passive"))
    )
    (net (code "65") (name "Net-(LED3-PadC)") (class "Default")
      (node (ref "LED3") (pin "C") (pinfunction "C_C") (pintype "passive"))
      (node (ref "R14") (pin "2") (pinfunction "2_2") (pintype "passive"))
    )
    (net (code "66") (name "Net-(LED4-PadC)") (class "Default")
      (node (ref "LED4") (pin "C") (pinfunction "C_C") (pintype "passive"))
      (node (ref "R28") (pin "2") (pinfunction "2_2") (pintype "passive"))
    )
    (net (code "67") (name "Net-(LED5-PadC)") (class "Default")
      (node (ref "LED5") (pin "C") (pinfunction "C_C") (pintype "passive"))
      (node (ref "R29") (pin "2") (pinfunction "2_2") (pintype "passive"))
    )
    (net (code "68") (name "Net-(LED6-PadC)") (class "Default")
      (node (ref "LED6") (pin "C") (pinfunction "C_C") (pintype "passive"))
      (node (ref "R30") (pin "2") (pinfunction "2_2") (pintype "passive"))
    )
    (net (code "69") (name "Net-(LED7-PadC)") (class "Default")
      (node (ref "LED7") (pin "C") (pinfunction "C_C") (pintype "passive"))
      (node (ref "R31") (pin "2") (pinfunction "2_2") (pintype "passive"))
    )
    (net (code "70") (name "Net-(R19-Pad1)") (class "Default")
      (node (ref "R19") (pin "1") (pinfunction "1_1") (pintype "passive"))
      (node (ref "SG1") (pin "1") (pinfunction "1_1") (pintype "passive"))
    )
    (net (code "71") (name "Net-(U$5-BOOT)") (class "Default")
      (node (ref "C28") (pin "2") (pinfunction "2_2") (pintype "passive"))
      (node (ref "U$5") (pin "1") (pinfunction "BOOT_1") (pintype "bidirectional"))
    )
    (net (code "72") (name "Net-(U$5-COMP)") (class "Default")
      (node (ref "C51") (pin "1") (pinfunction "1_1") (pintype "passive"))
      (node (ref "C52") (pin "1") (pinfunction "1_1") (pintype "passive"))
      (node (ref "U$5") (pin "6") (pinfunction "COMP_6") (pintype "bidirectional"))
    )
    (net (code "73") (name "Net-(U$5-EN)") (class "Default")
      (node (ref "R20") (pin "1") (pinfunction "1_1") (pintype "passive"))
      (node (ref "R45") (pin "2") (pinfunction "2_2") (pintype "passive"))
      (node (ref "U$5") (pin "3") (pinfunction "EN_3") (pintype "bidirectional"))
    )
    (net (code "74") (name "Net-(U$5-SS)") (class "Default")
      (node (ref "C55") (pin "2") (pinfunction "2_2") (pintype "passive"))
      (node (ref "U$5") (pin "4") (pinfunction "SS_4") (pintype "bidirectional"))
    )
    (net (code "75") (name "Net-(U$5-VSENSE)") (class "Default")
      (node (ref "R37") (pin "1") (pinfunction "1_1") (pintype "passive"))
      (node (ref "R38") (pin "2") (pinfunction "2_2") (pintype "passive"))
      (node (ref "U$5") (pin "5") (pinfunction "VSENSE_5") (pintype "bidirectional"))
    )
    (net (code "76") (name "Net-(U$14-P14{slash}~{CTS1}{slash}~{RTS1}{slash}~{SS1}{slash}CTX1{slash}USB0_DPUPE{slash}IRQ4)") (class "Default")
      (node (ref "R10") (pin "1") (pinfunction "1_1") (pintype "passive"))
      (node (ref "U$14") (pin "32") (pinfunction "P14/~{CTS1}/~{RTS1}/~{SS1}/CTX1/USB0_DPUPE/IRQ4_32") (pintype "bidirectional"))
    )
    (net (code "77") (name "Net-(U$14-VCL)") (class "Default")
      (node (ref "C4") (pin "2") (pinfunction "2_2") (pintype "passive"))
      (node (ref "U$14") (pin "5") (pinfunction "VCL_5") (pintype "bidirectional"))
    )
    (net (code "78") (name "Net-(U$16-BOOT)") (class "Default")
      (node (ref "C27") (pin "1") (pinfunction "1_1") (pintype "passive"))
      (node (ref "U$16") (pin "P$7") (pinfunction "BOOT_P$7") (pintype "bidirectional"))
    )
    (net (code "79") (name "Net-(U$16-BOOT_R)") (class "Default")
      (node (ref "C27") (pin "2") (pinfunction "2_2") (pintype "passive"))
      (node (ref "U$16") (pin "P$6") (pinfunction "BOOT_R_P$6") (pintype "bidirectional"))
    )
    (net (code "80") (name "Net-(U$17-BOOT)") (class "Default")
      (node (ref "C31") (pin "1") (pinfunction "1_1") (pintype "passive"))
      (node (ref "U$17") (pin "P$7") (pinfunction "BOOT_P$7") (pintype "bidirectional"))
    )
    (net (code "81") (name "Net-(U$17-BOOT_R)") (class "Default")
      (node (ref "C31") (pin "2") (pinfunction "2_2") (pintype "passive"))
      (node (ref "U$17") (pin "P$6") (pinfunction "BOOT_R_P$6") (pintype "bidirectional"))
    )
    (net (code "82") (name "Net-(U$18-BOOT)") (class "Default")
      (node (ref "C34") (pin "1") (pinfunction "1_1") (pintype "passive"))
      (node (ref "U$18") (pin "P$7") (pinfunction "BOOT_P$7") (pintype "bidirectional"))
    )
    (net (code "83") (name "Net-(U$18-BOOT_R)") (class "Default")
      (node (ref "C34") (pin "2") (pinfunction "2_2") (pintype "passive"))
      (node (ref "U$18") (pin "P$6") (pinfunction "BOOT_R_P$6") (pintype "bidirectional"))
    )
    (net (code "84") (name "Net-(U$19-BOOT)") (class "Default")
      (node (ref "C37") (pin "1") (pinfunction "1_1") (pintype "passive"))
      (node (ref "U$19") (pin "P$7") (pinfunction "BOOT_P$7") (pintype "bidirectional"))
    )
    (net (code "85") (name "Net-(U$19-BOOT_R)") (class "Default")
      (node (ref "C37") (pin "2") (pinfunction "2_2") (pintype "passive"))
      (node (ref "U$19") (pin "P$6") (pinfunction "BOOT_R_P$6") (pintype "bidirectional"))
    )
    (net (code "86") (name "OUT1_EN") (class "Default")
      (node (ref "U$14") (pin "55") (pinfunction "PB5/A13/SCK9_55") (pintype "bidirectional"))
      (node (ref "X2") (pin "18") (pinfunction "KL_18") (pintype "passive"))
    )
    (net (code "87") (name "OUT2_EN") (class "Default")
      (node (ref "U$14") (pin "53") (pinfunction "PB7/A15/TXD9/SMOSI9/SSDA9_53") (pintype "bidirectional"))
      (node (ref "X2") (pin "20") (pinfunction "KL_20") (pintype "passive"))
    )
    (net (code "88") (name "OUT3_EN") (class "Default")
      (node (ref "U$14") (pin "4") (pinfunction "PJ3/MTIOC3C/~{CTS6}/~{RTS6}/~{CTS0}/~{RTS0}/~{SS6}/~{SS0}_4") (pintype "bidirectional"))
      (node (ref "X2") (pin "22") (pinfunction "KL_22") (pintype "passive"))
    )
    (net (code "89") (name "OUT4_EN") (class "Default")
      (node (ref "U$14") (pin "41") (pinfunction "BCLK/P53_41") (pintype "bidirectional"))
      (node (ref "X2") (pin "24") (pinfunction "KL_24") (pintype "passive"))
    )
    (net (code "90") (name "OUT5_EN") (class "Default")
      (node (ref "U$14") (pin "98") (pinfunction "P07/IRQ15/~{ADTRG0}_98") (pintype "bidirectional"))
      (node (ref "X2") (pin "26") (pinfunction "KL_26") (pintype "passive"))
    )
    (net (code "91") (name "PGOOD1") (class "Default")
      (node (ref "U$14") (pin "49") (pinfunction "A19/TXD5/SMOSI5/SSDA5/IETXD_49") (pintype "bidirectional"))
      (node (ref "X2") (pin "31") (pinfunction "KL_31") (pintype "passive"))
    )
    (net (code "92") (name "PGOOD2") (class "Default")
      (node (ref "U$14") (pin "50") (pinfunction "PC2/A18/RXD5/SMISO5/SSCL5/SSLA3/IERXD_50") (pintype "bidirectional"))
      (node (ref "X2") (pin "33") (pinfunction "KL_33") (pintype "passive"))
    )
    (net (code "93") (name "PWM0") (class "Default")
      (node (ref "U$14") (pin "70") (pinfunction "PA0/A0/~{BC0}/SSLA1_70") (pintype "bidirectional"))
      (node (ref "U$16") (pin "P$8") (pinfunction "PWM_P$8") (pintype "bidirectional"))
    )
    (net (code "94") (name "PWM1") (class "Default")
      (node (ref "U$14") (pin "66") (pinfunction "PA4/A4/TXD5/SMOSI5/SSDA5/SSLA0/IRQ5-DS_66") (pintype "bidirectional"))
      (node (ref "U$17") (pin "P$8") (pinfunction "PWM_P$8") (pintype "bidirectional"))
    )
    (net (code "95") (name "PWM2") (class "Default")
      (node (ref "U$14") (pin "64") (pinfunction "PA6/A6/~{CTS5}/~{RTS5}/~{SS5}/MOSIA_64") (pintype "bidirectional"))
      (node (ref "U$18") (pin "P$8") (pinfunction "PWM_P$8") (pintype "bidirectional"))
    )
    (net (code "96") (name "PWM3") (class "Default")
      (node (ref "U$14") (pin "61") (pinfunction "PB0/A8/RXD6/SMISO6/SSCL6/RSPCKA/IRQ12_61") (pintype "bidirectional"))
      (node (ref "U$19") (pin "P$8") (pinfunction "PWM_P$8") (pintype "bidirectional"))
    )
    (net (code "97") (name "PWM4") (class "Default")
      (node (ref "U$14") (pin "56") (pinfunction "PB4/A12/~{CTS9}/~{RTS9}/~{SS9}_56") (pintype "bidirectional"))
      (node (ref "X2") (pin "34") (pinfunction "KL_34") (pintype "passive"))
    )
    (net (code "98") (name "PWM5") (class "Default")
      (node (ref "U$14") (pin "54") (pinfunction "PB6/A14/RXD9/SMISO9/SSCL9_54") (pintype "bidirectional"))
      (node (ref "X2") (pin "32") (pinfunction "KL_32") (pintype "passive"))
    )
    (net (code "99") (name "REGOUT1") (class "Default")
      (node (ref "C19") (pin "1") (pinfunction "1_1") (pintype "passive"))
      (node (ref "U1") (pin "10") (pinfunction "REGOUT_10") (pintype "bidirectional"))
    )
    (net (code "100") (name "REGOUT2") (class "Default")
      (node (ref "C24") (pin "1") (pinfunction "1_1") (pintype "passive"))
      (node (ref "U2") (pin "10") (pinfunction "REGOUT_10") (pintype "bidirectional"))
    )
    (net (code "101") (name "RSPCKA") (class "Default")
      (node (ref "U$14") (pin "47") (pinfunction "PC5/A21/~{CS2}/~{WAIT}/SCK8/RSPCKA_47") (pintype "bidirectional"))
      (node (ref "U2") (pin "23") (pinfunction "SCL/SCLK_23") (pintype "bidirectional"))
    )
    (net (code "102") (name "RSPCKB") (class "Default")
      (node (ref "U$14") (pin "77") (pinfunction "PE1/D9[A9/D9]/TXD12/SMOSI12/SSDA12/TXDX12/SIOX12/SSLB2/RSPCKB/ANEX1_77") (pintype "bidirectional"))
      (node (ref "U1") (pin "23") (pinfunction "SCL/SCLK_23") (pintype "bidirectional"))
    )
    (net (code "103") (name "SSLA0") (class "Default")
      (node (ref "U$14") (pin "48") (pinfunction "PC4/A20/~{CS3}/SCK5/~{CTS8}/~{RTS8}/~{SS8}/SSLA0_48") (pintype "bidirectional"))
      (node (ref "U2") (pin "8") (pinfunction "CS_8") (pintype "bidirectional"))
    )
    (net (code "104") (name "SSLB0") (class "Default")
      (node (ref "U$14") (pin "74") (pinfunction "PE4/D12[A12/D12]/SSLB0/AN2_74") (pintype "bidirectional"))
      (node (ref "U1") (pin "8") (pinfunction "CS_8") (pintype "bidirectional"))
    )
    (net (code "105") (name "SUPERCAP") (class "Default")
      (node (ref "D7") (pin "3") (pinfunction "C_3") (pintype "passive"))
      (node (ref "U$1") (pin "P") (pinfunction "P_P") (pintype "bidirectional"))
      (node (ref "U$14") (pin "6") (pinfunction "VBATT_6") (pintype "bidirectional"))
    )
    (net (code "106") (name "USB0_DM") (class "Default")
      (node (ref "R24") (pin "1") (pinfunction "1_1") (pintype "passive"))
      (node (ref "U$14") (pin "36") (pinfunction "USB0_DM_36") (pintype "bidirectional"))
    )
    (net (code "107") (name "USB0_DP") (class "Default")
      (node (ref "R10") (pin "2") (pinfunction "2_2") (pintype "passive"))
      (node (ref "R25") (pin "1") (pinfunction "1_1") (pintype "passive"))
      (node (ref "U$14") (pin "37") (pinfunction "USB0_DP_37") (pintype "bidirectional"))
    )
    (net (code "108") (name "USB0_VBUS") (class "Default")
      (node (ref "R26") (pin "1") (pinfunction "1_1") (pintype "passive"))
      (node (ref "R27") (pin "2") (pinfunction "2_2") (pintype "passive"))
      (node (ref "U$14") (pin "30") (pinfunction "P16/TXD1/RXD3/SMOSI1/SMISO3/SSDA1/SSCL3/MOSIA/SCL2-DS/IERXD/USB0_VBUS/IRQ6/~{ADTRG0}_30") (pintype "bidirectional"))
    )
    (net (code "109") (name "V+") (class "Default")
      (node (ref "C56") (pin "1") (pinfunction "1_1") (pintype "passive"))
      (node (ref "C58") (pin "+") (pinfunction "+_+") (pintype "passive"))
      (node (ref "R20") (pin "2") (pinfunction "2_2") (pintype "passive"))
      (node (ref "U$5") (pin "2") (pinfunction "VIN_2") (pintype "bidirectional"))
      (node (ref "X2") (pin "12") (pinfunction "KL_12") (pintype "passive"))
    )
    (net (code "110") (name "VBAT0") (class "Default")
      (node (ref "C42") (pin "1") (pinfunction "1_1") (pintype "passive"))
      (node (ref "L2") (pin "2") (pinfunction "2_2") (pintype "passive"))
      (node (ref "R16") (pin "1") (pinfunction "1_1") (pintype "passive"))
      (node (ref "X2") (pin "1") (pinfunction "KL_1") (pintype "passive"))
      (node (ref "X2") (pin "2") (pinfunction "KL_2") (pintype "passive"))
    )
    (net (code "111") (name "VBAT0_AD") (class "Default")
      (node (ref "C15") (pin "1") (pinfunction "1_1") (pintype "passive"))
      (node (ref "R16") (pin "2") (pinfunction "2_2") (pintype "passive"))
      (node (ref "R17") (pin "1") (pinfunction "1_1") (pintype "passive"))
      (node (ref "U$14") (pin "95") (pinfunction "P40/IRQ8-DS/AN000_95") (pintype "bidirectional"))
    )
    (net (code "112") (name "VBAT1") (class "Default")
      (node (ref "C43") (pin "1") (pinfunction "1_1") (pintype "passive"))
      (node (ref "L3") (pin "2") (pinfunction "2_2") (pintype "passive"))
      (node (ref "R11") (pin "1") (pinfunction "1_1") (pintype "passive"))
      (node (ref "X2") (pin "3") (pinfunction "KL_3") (pintype "passive"))
      (node (ref "X2") (pin "4") (pinfunction "KL_4") (pintype "passive"))
    )
    (net (code "113") (name "VBAT1_AD") (class "Default")
      (node (ref "C8") (pin "1") (pinfunction "1_1") (pintype "passive"))
      (node (ref "R11") (pin "2") (pinfunction "2_2") (pintype "passive"))
      (node (ref "R13") (pin "1") (pinfunction "1_1") (pintype "passive"))
      (node (ref "U$14") (pin "93") (pinfunction "P41/IRQ9-DS/AN001_93") (pintype "bidirectional"))
    )
    (net (code "114") (name "VBAT2") (class "Default")
      (node (ref "C44") (pin "1") (pinfunction "1_1") (pintype "passive"))
      (node (ref "L4") (pin "2") (pinfunction "2_2") (pintype "passive"))
      (node (ref "R3") (pin "1") (pinfunction "1_1") (pintype "passive"))
      (node (ref "X2") (pin "5") (pinfunction "KL_5") (pintype "passive"))
      (node (ref "X2") (pin "6") (pinfunction "KL_6") (pintype "passive"))
    )
    (net (code "115") (name "VBAT2_AD") (class "Default")
      (node (ref "C2") (pin "1") (pinfunction "1_1") (pintype "passive"))
      (node (ref "R3") (pin "2") (pinfunction "2_2") (pintype "passive"))
      (node (ref "R4") (pin "1") (pinfunction "1_1") (pintype "passive"))
      (node (ref "U$14") (pin "92") (pinfunction "P42/IRQ10-DS/AN002_92") (pintype "bidirectional"))
    )
    (net (code "116") (name "VBAT3") (class "Default")
      (node (ref "C45") (pin "1") (pinfunction "1_1") (pintype "passive"))
      (node (ref "L5") (pin "2") (pinfunction "2_2") (pintype "passive"))
      (node (ref "R1") (pin "1") (pinfunction "1_1") (pintype "passive"))
      (node (ref "X2") (pin "7") (pinfunction "KL_7") (pintype "passive"))
      (node (ref "X2") (pin "8") (pinfunction "KL_8") (pintype "passive"))
    )
    (net (code "117") (name "VBAT3_AD") (class "Default")
      (node (ref "C1") (pin "1") (pinfunction "1_1") (pintype "passive"))
      (node (ref "R1") (pin "2") (pinfunction "2_2") (pintype "passive"))
      (node (ref "R2") (pin "1") (pinfunction "1_1") (pintype "passive"))
      (node (ref "U$14") (pin "91") (pinfunction "P43/IRQ11-DS/AN003_91") (pintype "bidirectional"))
    )
    (net (code "118") (name "VBUS") (class "Default")
      (node (ref "D2") (pin "A") (pinfunction "A_A") (pintype "passive"))
      (node (ref "R27") (pin "1") (pinfunction "1_1") (pintype "passive"))
      (node (ref "U$2") (pin "VBUS") (pinfunction "VBUS_VBUS") (pintype "bidirectional"))
    )
    (net (code "119") (name "VIN") (class "Default")
      (node (ref "C30") (pin "1") (pinfunction "1_1") (pintype "passive"))
      (node (ref "C33") (pin "1") (pinfunction "1_1") (pintype "passive"))
      (node (ref "C36") (pin "1") (pinfunction "1_1") (pintype "passive"))
      (node (ref "C39") (pin "1") (pinfunction "1_1") (pintype "passive"))
      (node (ref "C50") (pin "1") (pinfunction "1_1") (pintype "passive"))
      (node (ref "D1") (pin "C") (pinfunction "C_C") (pintype "passive"))
      (node (ref "U$16") (pin "P$5A") (pinfunction "VIN_P$5A") (pintype "bidirectional"))
      (node (ref "U$16") (pin "P$5B") (pinfunction "VIN1_P$5B") (pintype "bidirectional"))
      (node (ref "U$16") (pin "P$5C") (pinfunction "VIN2_P$5C") (pintype "bidirectional"))
      (node (ref "U$16") (pin "P$5D") (pinfunction "VIN3_P$5D") (pintype "bidirectional"))
      (node (ref "U$16") (pin "P$5E") (pinfunction "VIN4_P$5E") (pintype "bidirectional"))
      (node (ref "U$16") (pin "P$5F") (pinfunction "VIN5_P$5F") (pintype "bidirectional"))
      (node (ref "U$17") (pin "P$5A") (pinfunction "VIN_P$5A") (pintype "bidirectional"))
      (node (ref "U$17") (pin "P$5B") (pinfunction "VIN1_P$5B") (pintype "bidirectional"))
      (node (ref "U$17") (pin "P$5C") (pinfunction "VIN2_P$5C") (pintype "bidirectional"))
      (node (ref "U$17") (pin "P$5D") (pinfunction "VIN3_P$5D") (pintype "bidirectional"))
      (node (ref "U$17") (pin "P$5E") (pinfunction "VIN4_P$5E") (pintype "bidirectional"))
      (node (ref "U$17") (pin "P$5F") (pinfunction "VIN5_P$5F") (pintype "bidirectional"))
      (node (ref "U$18") (pin "P$5A") (pinfunction "VIN_P$5A") (pintype "bidirectional"))
      (node (ref "U$18") (pin "P$5B") (pinfunction "VIN1_P$5B") (pintype "bidirectional"))
      (node (ref "U$18") (pin "P$5C") (pinfunction "VIN2_P$5C") (pintype "bidirectional"))
      (node (ref "U$18") (pin "P$5D") (pinfunction "VIN3_P$5D") (pintype "bidirectional"))
      (node (ref "U$18") (pin "P$5E") (pinfunction "VIN4_P$5E") (pintype "bidirectional"))
      (node (ref "U$18") (pin "P$5F") (pinfunction "VIN5_P$5F") (pintype "bidirectional"))
      (node (ref "U$19") (pin "P$5A") (pinfunction "VIN_P$5A") (pintype "bidirectional"))
      (node (ref "U$19") (pin "P$5B") (pinfunction "VIN1_P$5B") (pintype "bidirectional"))
      (node (ref "U$19") (pin "P$5C") (pinfunction "VIN2_P$5C") (pintype "bidirectional"))
      (node (ref "U$19") (pin "P$5D") (pinfunction "VIN3_P$5D") (pintype "bidirectional"))
      (node (ref "U$19") (pin "P$5E") (pinfunction "VIN4_P$5E") (pintype "bidirectional"))
      (node (ref "U$19") (pin "P$5F") (pinfunction "VIN5_P$5F") (pintype "bidirectional"))
    )
    (net (code "120") (name "VSW0") (class "Default")
      (node (ref "L2") (pin "1") (pinfunction "1_1") (pintype "passive"))
      (node (ref "U$16") (pin "P$4A") (pinfunction "VSW_P$4A") (pintype "bidirectional"))
      (node (ref "U$16") (pin "P$4B") (pinfunction "VSW1_P$4B") (pintype "bidirectional"))
      (node (ref "U$16") (pin "P$4C") (pinfunction "VSW2_P$4C") (pintype "bidirectional"))
      (node (ref "U$16") (pin "P$4D") (pinfunction "VSW3_P$4D") (pintype "bidirectional"))
      (node (ref "U$16") (pin "P$4E") (pinfunction "VSW4_P$4E") (pintype "bidirectional"))
      (node (ref "U$16") (pin "P$4F") (pinfunction "VSW5_P$4F") (pintype "bidirectional"))
    )
    (net (code "121") (name "VSW1") (class "Default")
      (node (ref "L3") (pin "1") (pinfunction "1_1") (pintype "passive"))
      (node (ref "U$17") (pin "P$4A") (pinfunction "VSW_P$4A") (pintype "bidirectional"))
      (node (ref "U$17") (pin "P$4B") (pinfunction "VSW1_P$4B") (pintype "bidirectional"))
      (node (ref "U$17") (pin "P$4C") (pinfunction "VSW2_P$4C") (pintype "bidirectional"))
      (node (ref "U$17") (pin "P$4D") (pinfunction "VSW3_P$4D") (pintype "bidirectional"))
      (node (ref "U$17") (pin "P$4E") (pinfunction "VSW4_P$4E") (pintype "bidirectional"))
      (node (ref "U$17") (pin "P$4F") (pinfunction "VSW5_P$4F") (pintype "bidirectional"))
    )
    (net (code "122") (name "VSW2") (class "Default")
      (node (ref "L4") (pin "1") (pinfunction "1_1") (pintype "passive"))
      (node (ref "U$18") (pin "P$4A") (pinfunction "VSW_P$4A") (pintype "bidirectional"))
      (node (ref "U$18") (pin "P$4B") (pinfunction "VSW1_P$4B") (pintype "bidirectional"))
      (node (ref "U$18") (pin "P$4C") (pinfunction "VSW2_P$4C") (pintype "bidirectional"))
      (node (ref "U$18") (pin "P$4D") (pinfunction "VSW3_P$4D") (pintype "bidirectional"))
      (node (ref "U$18") (pin "P$4E") (pinfunction "VSW4_P$4E") (pintype "bidirectional"))
      (node (ref "U$18") (pin "P$4F") (pinfunction "VSW5_P$4F") (pintype "bidirectional"))
    )
    (net (code "123") (name "VSW3") (class "Default")
      (node (ref "L5") (pin "1") (pinfunction "1_1") (pintype "passive"))
      (node (ref "U$19") (pin "P$4A") (pinfunction "VSW_P$4A") (pintype "bidirectional"))
      (node (ref "U$19") (pin "P$4B") (pinfunction "VSW1_P$4B") (pintype "bidirectional"))
      (node (ref "U$19") (pin "P$4C") (pinfunction "VSW2_P$4C") (pintype "bidirectional"))
      (node (ref "U$19") (pin "P$4D") (pinfunction "VSW3_P$4D") (pintype "bidirectional"))
      (node (ref "U$19") (pin "P$4E") (pinfunction "VSW4_P$4E") (pintype "bidirectional"))
      (node (ref "U$19") (pin "P$4F") (pinfunction "VSW5_P$4F") (pintype "bidirectional"))
    )
    (net (code "124") (name "XCIN") (class "Default")
      (node (ref "C9") (pin "2") (pinfunction "2_2") (pintype "passive"))
      (node (ref "Q1") (pin "1") (pinfunction "1_1") (pintype "passive"))
      (node (ref "U$14") (pin "8") (pinfunction "XCIN_8") (pintype "bidirectional"))
    )
    (net (code "125") (name "XCOUT") (class "Default")
      (node (ref "C11") (pin "2") (pinfunction "2_2") (pintype "passive"))
      (node (ref "Q1") (pin "4") (pinfunction "2_4") (pintype "passive"))
      (node (ref "U$14") (pin "9") (pinfunction "XCOUT_9") (pintype "bidirectional"))
    )
    (net (code "126") (name "XTAL") (class "Default")
      (node (ref "C6") (pin "2") (pinfunction "2_2") (pintype "passive"))
      (node (ref "U$14") (pin "11") (pinfunction "XTAL/P37_11") (pintype "bidirectional"))
      (node (ref "X1") (pin "P$1") (pinfunction "P$1_P$1") (pintype "bidirectional"))
    )
    (net (code "127") (name "unconnected-(JP2-Pad6)") (class "Default")
      (node (ref "JP2") (pin "6") (pinfunction "6_6") (pintype "passive"))
    )
    (net (code "128") (name "unconnected-(U$3-NC-PadP$3)") (class "Default")
      (node (ref "U$3") (pin "P$3") (pinfunction "NC_P$3") (pintype "bidirectional"))
    )
    (net (code "129") (name "unconnected-(U$6-CE-PadP$4)") (class "Default")
      (node (ref "U$6") (pin "P$4") (pinfunction "CE_P$4") (pintype "bidirectional"))
    )
    (net (code "130") (name "unconnected-(U1-AUXCL-Pad7)") (class "Default")
      (node (ref "U1") (pin "7") (pinfunction "AUXCL_7") (pintype "bidirectional"))
    )
    (net (code "131") (name "unconnected-(U1-AUXDA-Pad6)") (class "Default")
      (node (ref "U1") (pin "6") (pinfunction "AUXDA_6") (pintype "bidirectional"))
    )
    (net (code "132") (name "unconnected-(U1-CLKOUT-Pad22)") (class "Default")
      (node (ref "U1") (pin "22") (pinfunction "CLKOUT_22") (pintype "bidirectional"))
    )
    (net (code "133") (name "unconnected-(U2-AUXCL-Pad7)") (class "Default")
      (node (ref "U2") (pin "7") (pinfunction "AUXCL_7") (pintype "bidirectional"))
    )
    (net (code "134") (name "unconnected-(U2-AUXDA-Pad6)") (class "Default")
      (node (ref "U2") (pin "6") (pinfunction "AUXDA_6") (pintype "bidirectional"))
    )
    (net (code "135") (name "unconnected-(U2-CLKOUT-Pad22)") (class "Default")
      (node (ref "U2") (pin "22") (pinfunction "CLKOUT_22") (pintype "bidirectional"))
    )
    (net (code "136") (name "~{OLED_CS}") (class "Default")
      (node (ref "JP2") (pin "10") (pinfunction "10_10") (pintype "passive"))
      (node (ref "U$14") (pin "39") (pinfunction "P55/~{WAIT}/CRX1/IRQ10_39") (pintype "bidirectional"))
      (node (ref "U$3") (pin "P$16") (pinfunction "~{CS}_P$16") (pintype "bidirectional"))
    )
    (net (code "137") (name "~{OLED_DC}") (class "Default")
      (node (ref "U$14") (pin "40") (pinfunction "P54/ALE/~{CTS2}/~{RTS2}/~{SS2}/CTX1_40") (pintype "bidirectional"))
      (node (ref "U$3") (pin "P$14") (pinfunction "~{DC}_P$14") (pintype "bidirectional"))
    )
    (net (code "138") (name "~{OLED_RD}") (class "Default")
      (node (ref "U$14") (pin "42") (pinfunction "P52/~{RD}/RXD2/SMISO2/SSCL2/SSLB3_42") (pintype "bidirectional"))
      (node (ref "U$3") (pin "P$12") (pinfunction "~{RD}_P$12") (pintype "bidirectional"))
    )
    (net (code "139") (name "~{OLED_RESET}") (class "Default")
      (node (ref "U$14") (pin "43") (pinfunction "P51/~{WR1}/~{BC1}/~{WAIT}/SCK2/SSLB2_43") (pintype "bidirectional"))
      (node (ref "U$3") (pin "P$15") (pinfunction "~{RESET}_P$15") (pintype "bidirectional"))
    )
    (net (code "140") (name "~{OLED_WR}") (class "Default")
      (node (ref "U$14") (pin "44") (pinfunction "P50/~{WR0}/~{WR}/TXD2/SMOSI2/SSDA2/SSLB1_44") (pintype "bidirectional"))
      (node (ref "U$3") (pin "P$13") (pinfunction "~{WR}_P$13") (pintype "bidirectional"))
    )
    (net (code "141") (name "~{RESET}") (class "Default")
      (node (ref "JP2") (pin "13") (pinfunction "13_13") (pintype "passive"))
      (node (ref "R22") (pin "2") (pinfunction "2_2") (pintype "passive"))
      (node (ref "S9") (pin "1") (pinfunction "1_1") (pintype "passive"))
      (node (ref "U$14") (pin "10") (pinfunction "~{RES}_10") (pintype "bidirectional"))
    )
    (net (code "142") (name "~{SKIP0}") (class "Default")
      (node (ref "U$14") (pin "69") (pinfunction "PA1/A1/SCK5/SSLA2/IRQ11_69") (pintype "bidirectional"))
      (node (ref "U$16") (pin "P$1") (pinfunction "~{SKIP}_P$1") (pintype "bidirectional"))
    )
    (net (code "143") (name "~{SKIP1}") (class "Default")
      (node (ref "U$14") (pin "68") (pinfunction "PA2/A2/PO18/RXD5/SMISO5/SSCL5/SSLA3_68") (pintype "bidirectional"))
      (node (ref "U$17") (pin "P$1") (pinfunction "~{SKIP}_P$1") (pintype "bidirectional"))
    )
    (net (code "144") (name "~{SKIP2}") (class "Default")
      (node (ref "U$14") (pin "67") (pinfunction "PA3/A3/RXD5/SMISO5/SSCL5/IRQ6-DS_67") (pintype "bidirectional"))
      (node (ref "U$18") (pin "P$1") (pinfunction "~{SKIP}_P$1") (pintype "bidirectional"))
    )
    (net (code "145") (name "~{SKIP3}") (class "Default")
      (node (ref "U$14") (pin "65") (pinfunction "PA5/A5/RSPCKA_65") (pintype "bidirectional"))
      (node (ref "U$19") (pin "P$1") (pinfunction "~{SKIP}_P$1") (pintype "bidirectional"))
    )
    (net (code "146") (name "~{SW1}") (class "Default")
      (node (ref "S6") (pin "3") (pinfunction "3_3") (pintype "passive"))
      (node (ref "S6") (pin "4") (pinfunction "4_4") (pintype "passive"))
      (node (ref "U$14") (pin "17") (pinfunction "P33/MTIOC0D/TIOCD0/TMRI3/PO11/RXD6/RXD0/SMISO6/SMISO0/SSCL6/SSCL0/IRQ3-DS_17") (pintype "bidirectional"))
    )
    (net (code "147") (name "~{SW2}") (class "Default")
      (node (ref "S7") (pin "3") (pinfunction "3_3") (pintype "passive"))
      (node (ref "S7") (pin "4") (pinfunction "4_4") (pintype "passive"))
      (node (ref "U$14") (pin "18") (pinfunction "P32/TXD6/TXD0/SMOSI6/SMOSI0/SSDA6/SSDA0/IRQ3-DS_18") (pintype "bidirectional"))
    )
    (net (code "148") (name "~{SW3}{slash}TMS") (class "Default")
      (node (ref "JP2") (pin "9") (pinfunction "9_9") (pintype "passive"))
      (node (ref "S8") (pin "3") (pinfunction "3_3") (pintype "passive"))
      (node (ref "S8") (pin "4") (pinfunction "4_4") (pintype "passive"))
      (node (ref "U$14") (pin "19") (pinfunction "~{CTS1}/~{RTS1}/~{SS1}/SSLB0/IRQ1-DS_19") (pintype "bidirectional"))
    )
    (net (code "149") (name "~{SW4}{slash}TDI") (class "Default")
      (node (ref "S2") (pin "3") (pinfunction "3_3") (pintype "passive"))
      (node (ref "S2") (pin "4") (pinfunction "4_4") (pintype "passive"))
      (node (ref "U$14") (pin "20") (pinfunction "P30/RXD1/SMISO1/SSCL1/MISOB/IRQ0-DS_20") (pintype "bidirectional"))
    )
    (net (code "150") (name "~{TRST}") (class "Default")
      (node (ref "JP2") (pin "3") (pinfunction "3_3") (pintype "passive"))
      (node (ref "U$14") (pin "16") (pinfunction "~{TRST}/P34/MTIOC0A/TMCI3/PO12/~{POE2}/SCK6/SCK0/IRQ4_16") (pintype "bidirectional"))
      (node (ref "X3") (pin "1") (pinfunction "S_1") (pintype "passive"))
    )
  )
)
